# Power_Meter.net
KiCad netlist of a schematic drawn in Altium Designer
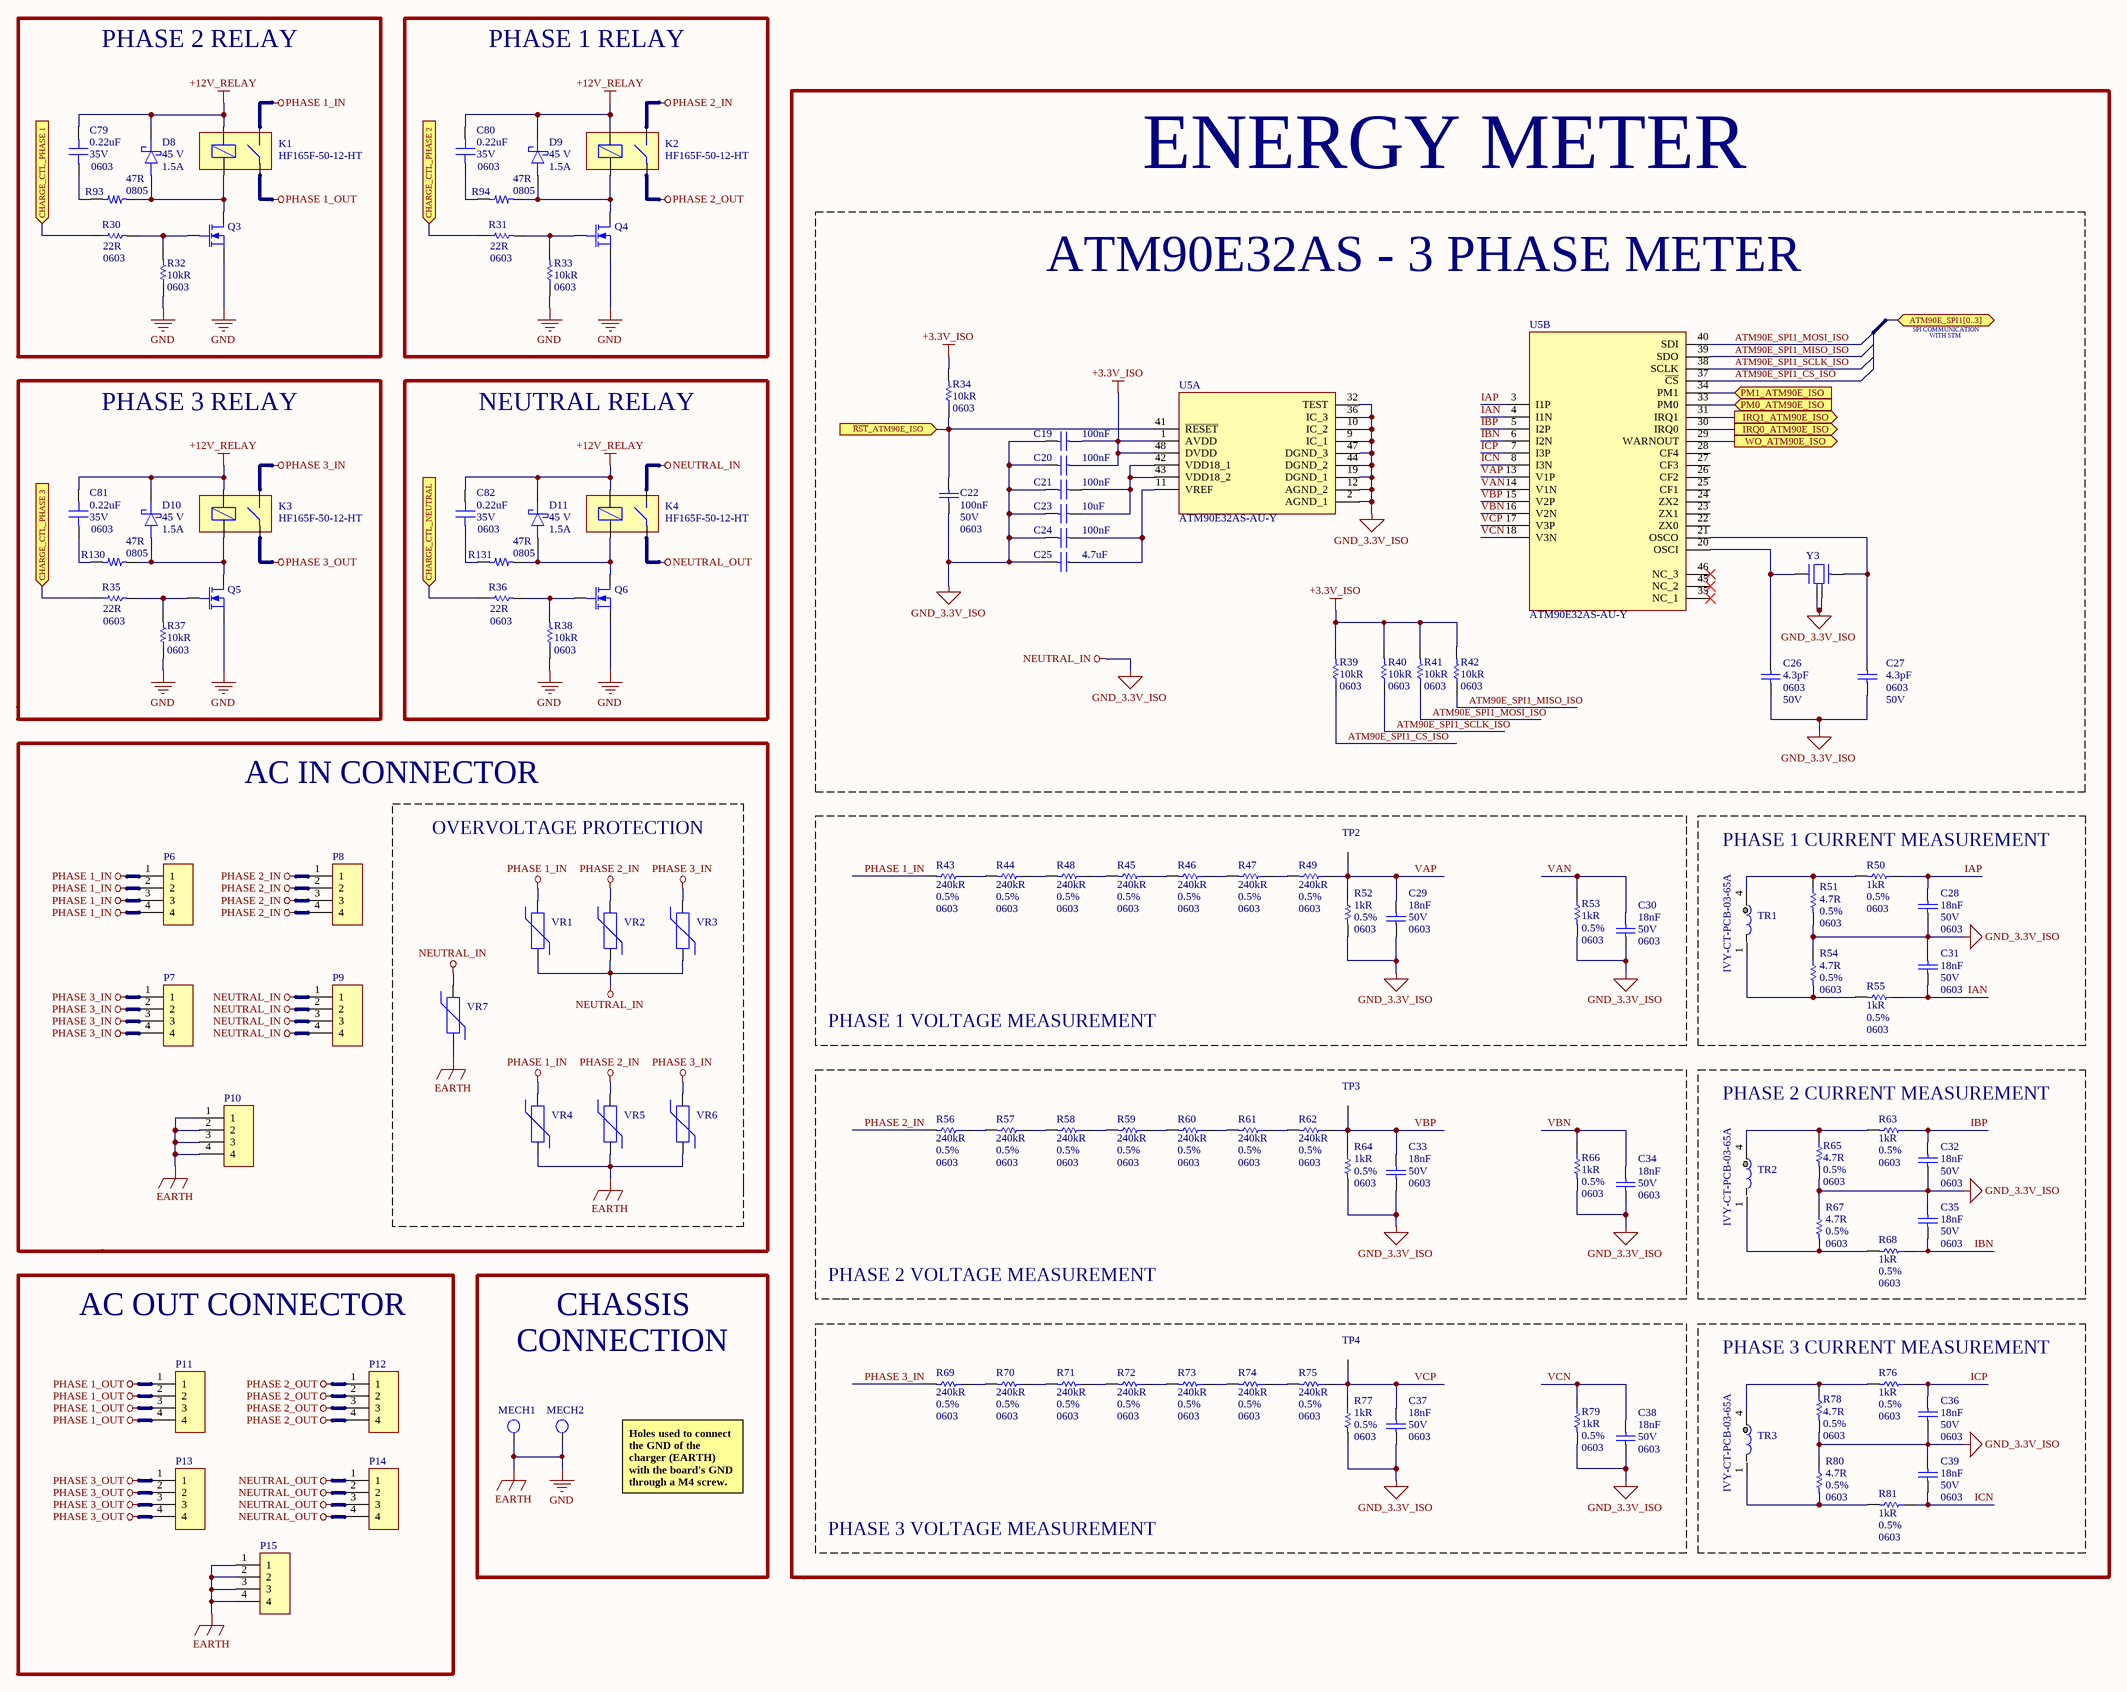
[diagram p0: Power Meter.SchDoc]

(export (version "E")
  (design (tool "Eeschema 10.0.6"))
  (components
    (comp (ref "C19")
      (value "100nF")
      (footprint "C0603")
      (description "Cap Ceramic 50V 20% +Tol 20% -Tol X7R 15% TC 0.1uF SMD 0603")
      (fields
        (field (name "MANUFACTURER") "Yageo")
        (field (name "MANUFACTURER PART NUMBER") "CC0603MRX7R9BB104")
      )
      (libsource (lib "Power2Go - REV05") (part "C_0603_0.1uF_50V_20%"))
    )
    (comp (ref "C20")
      (value "100nF")
      (footprint "C0603")
      (description "Cap Ceramic 50V 20% +Tol 20% -Tol X7R 15% TC 0.1uF SMD 0603")
      (fields
        (field (name "MANUFACTURER") "Yageo")
        (field (name "MANUFACTURER PART NUMBER") "CC0603MRX7R9BB104")
      )
      (libsource (lib "Power2Go - REV05") (part "C_0603_0.1uF_50V_20%"))
    )
    (comp (ref "C21")
      (value "100nF")
      (footprint "C0603")
      (description "Cap Ceramic 50V 20% +Tol 20% -Tol X7R 15% TC 0.1uF SMD 0603")
      (fields
        (field (name "MANUFACTURER") "Yageo")
        (field (name "MANUFACTURER PART NUMBER") "CC0603MRX7R9BB104")
      )
      (libsource (lib "Power2Go - REV05") (part "C_0603_0.1uF_50V_20%"))
    )
    (comp (ref "C22")
      (value "100nF")
      (footprint "C0603")
      (description "Cap Ceramic 50V 20% +Tol 20% -Tol X7R 15% TC 0.1uF SMD 0603")
      (fields
        (field (name "MANUFACTURER") "Yageo")
        (field (name "MANUFACTURER PART NUMBER") "CC0603MRX7R9BB104")
        (field (name "CASE/PACKAGE") "0603")
        (field (name "VOLTAGE RATING") "50V")
      )
      (libsource (lib "Power2Go - REV05") (part "C_0603_0.1uF_50V_20%"))
    )
    (comp (ref "C23")
      (value "C_0603_10uF_35V_20%")
      (footprint "C0603")
      (description "Cap Ceramic 10uF 35V X5R 20% Pad SMD 0603 85C T/R")
      (fields
        (field (name "MANUFACTURER") "Murata")
        (field (name "MANUFACTURER PART NUMBER") "GRM188R6YA106MA73D")
        (field (name "CAPACITANCE") "10uF")
      )
      (libsource (lib "Power2Go - REV05") (part "C_0603_10uF_35V_20%"))
    )
    (comp (ref "C24")
      (value "100nF")
      (footprint "C0603")
      (description "Cap Ceramic 50V 20% +Tol 20% -Tol X7R 15% TC 0.1uF SMD 0603")
      (fields
        (field (name "MANUFACTURER") "Yageo")
        (field (name "MANUFACTURER PART NUMBER") "CC0603MRX7R9BB104")
      )
      (libsource (lib "Power2Go - REV05") (part "C_0603_0.1uF_50V_20%"))
    )
    (comp (ref "C25")
      (value "4.7uF")
      (footprint "C0603")
      (description "CAP CER 4.7UF 16V X5R 0603")
      (fields
        (field (name "MANUFACTURER") "Samsung")
        (field (name "MANUFACTURER PART NUMBER") "CL10A475KO8NNNC")
      )
      (libsource (lib "Power2Go - REV05") (part "C_0603_4.7uF_16V_10%"))
    )
    (comp (ref "C26")
      (value "4.3pF")
      (footprint "C0603")
      (description "Cap Ceramic 4.3pF 50V C0G 0.25pF Pad SMD 0603 125C T/R")
      (fields
        (field (name "MANUFACTURER") "Yageo")
        (field (name "MANUFACTURER PART NUMBER") "CC0603CRNPO9BN4R3")
        (field (name "CASE CODE (IMPERIAL)") "0603")
        (field (name "VOLTAGE RATING") "50V")
      )
      (libsource (lib "Power2Go - REV05") (part "C_0603_4.3pF_±0.25pF_50V"))
    )
    (comp (ref "C27")
      (value "4.3pF")
      (footprint "C0603")
      (description "Cap Ceramic 4.3pF 50V C0G 0.25pF Pad SMD 0603 125C T/R")
      (fields
        (field (name "MANUFACTURER") "Yageo")
        (field (name "MANUFACTURER PART NUMBER") "CC0603CRNPO9BN4R3")
        (field (name "CASE CODE (IMPERIAL)") "0603")
        (field (name "VOLTAGE RATING") "50V")
      )
      (libsource (lib "Power2Go - REV05") (part "C_0603_4.3pF_±0.25pF_50V"))
    )
    (comp (ref "C28")
      (value "18nF")
      (footprint "C0603")
      (description "0603 18 nF 50 V ±5 % Tolerance X7R SMT Multilayer Ceramic Capacitor")
      (fields
        (field (name "MANUFACTURER") "Yageo")
        (field (name "MANUFACTURER PART NUMBER") "CC0603JRX7R9BB183")
        (field (name "VOLTAGE RATING") "50V")
        (field (name "CASE/PACKAGE") "0603")
      )
      (libsource (lib "Power2Go - REV05") (part "C_0603_0.018uF_50V_5%_"))
    )
    (comp (ref "C29")
      (value "18nF")
      (footprint "C0603")
      (description "0603 18 nF 50 V ±5 % Tolerance X7R SMT Multilayer Ceramic Capacitor")
      (fields
        (field (name "MANUFACTURER") "Yageo")
        (field (name "MANUFACTURER PART NUMBER") "CC0603JRX7R9BB183")
        (field (name "VOLTAGE RATING") "50V")
        (field (name "CASE/PACKAGE") "0603")
      )
      (libsource (lib "Power2Go - REV05") (part "C_0603_0.018uF_50V_5%_"))
    )
    (comp (ref "C30")
      (value "18nF")
      (footprint "C0603")
      (description "0603 18 nF 50 V ±5 % Tolerance X7R SMT Multilayer Ceramic Capacitor")
      (fields
        (field (name "MANUFACTURER") "Yageo")
        (field (name "MANUFACTURER PART NUMBER") "CC0603JRX7R9BB183")
        (field (name "VOLTAGE RATING") "50V")
        (field (name "CASE/PACKAGE") "0603")
      )
      (libsource (lib "Power2Go - REV05") (part "C_0603_0.018uF_50V_5%_"))
    )
    (comp (ref "C31")
      (value "18nF")
      (footprint "C0603")
      (description "0603 18 nF 50 V ±5 % Tolerance X7R SMT Multilayer Ceramic Capacitor")
      (fields
        (field (name "MANUFACTURER") "Yageo")
        (field (name "MANUFACTURER PART NUMBER") "CC0603JRX7R9BB183")
        (field (name "VOLTAGE RATING") "50V")
        (field (name "CASE/PACKAGE") "0603")
      )
      (libsource (lib "Power2Go - REV05") (part "C_0603_0.018uF_50V_5%_"))
    )
    (comp (ref "C32")
      (value "18nF")
      (footprint "C0603")
      (description "0603 18 nF 50 V ±5 % Tolerance X7R SMT Multilayer Ceramic Capacitor")
      (fields
        (field (name "MANUFACTURER") "Yageo")
        (field (name "MANUFACTURER PART NUMBER") "CC0603JRX7R9BB183")
        (field (name "VOLTAGE RATING") "50V")
        (field (name "CASE/PACKAGE") "0603")
      )
      (libsource (lib "Power2Go - REV05") (part "C_0603_0.018uF_50V_5%_"))
    )
    (comp (ref "C33")
      (value "18nF")
      (footprint "C0603")
      (description "0603 18 nF 50 V ±5 % Tolerance X7R SMT Multilayer Ceramic Capacitor")
      (fields
        (field (name "MANUFACTURER") "Yageo")
        (field (name "MANUFACTURER PART NUMBER") "CC0603JRX7R9BB183")
        (field (name "VOLTAGE RATING") "50V")
        (field (name "CASE/PACKAGE") "0603")
      )
      (libsource (lib "Power2Go - REV05") (part "C_0603_0.018uF_50V_5%_"))
    )
    (comp (ref "C34")
      (value "18nF")
      (footprint "C0603")
      (description "0603 18 nF 50 V ±5 % Tolerance X7R SMT Multilayer Ceramic Capacitor")
      (fields
        (field (name "MANUFACTURER") "Yageo")
        (field (name "MANUFACTURER PART NUMBER") "CC0603JRX7R9BB183")
        (field (name "VOLTAGE RATING") "50V")
        (field (name "CASE/PACKAGE") "0603")
      )
      (libsource (lib "Power2Go - REV05") (part "C_0603_0.018uF_50V_5%_"))
    )
    (comp (ref "C35")
      (value "18nF")
      (footprint "C0603")
      (description "0603 18 nF 50 V ±5 % Tolerance X7R SMT Multilayer Ceramic Capacitor")
      (fields
        (field (name "MANUFACTURER") "Yageo")
        (field (name "MANUFACTURER PART NUMBER") "CC0603JRX7R9BB183")
        (field (name "VOLTAGE RATING") "50V")
        (field (name "CASE/PACKAGE") "0603")
      )
      (libsource (lib "Power2Go - REV05") (part "C_0603_0.018uF_50V_5%_"))
    )
    (comp (ref "C36")
      (value "18nF")
      (footprint "C0603")
      (description "0603 18 nF 50 V ±5 % Tolerance X7R SMT Multilayer Ceramic Capacitor")
      (fields
        (field (name "MANUFACTURER") "Yageo")
        (field (name "MANUFACTURER PART NUMBER") "CC0603JRX7R9BB183")
        (field (name "VOLTAGE RATING") "50V")
        (field (name "CASE/PACKAGE") "0603")
      )
      (libsource (lib "Power2Go - REV05") (part "C_0603_0.018uF_50V_5%_"))
    )
    (comp (ref "C37")
      (value "18nF")
      (footprint "C0603")
      (description "0603 18 nF 50 V ±5 % Tolerance X7R SMT Multilayer Ceramic Capacitor")
      (fields
        (field (name "MANUFACTURER") "Yageo")
        (field (name "MANUFACTURER PART NUMBER") "CC0603JRX7R9BB183")
        (field (name "VOLTAGE RATING") "50V")
        (field (name "CASE/PACKAGE") "0603")
      )
      (libsource (lib "Power2Go - REV05") (part "C_0603_0.018uF_50V_5%_"))
    )
    (comp (ref "C38")
      (value "18nF")
      (footprint "C0603")
      (description "0603 18 nF 50 V ±5 % Tolerance X7R SMT Multilayer Ceramic Capacitor")
      (fields
        (field (name "MANUFACTURER") "Yageo")
        (field (name "MANUFACTURER PART NUMBER") "CC0603JRX7R9BB183")
        (field (name "VOLTAGE RATING") "50V")
        (field (name "CASE/PACKAGE") "0603")
      )
      (libsource (lib "Power2Go - REV05") (part "C_0603_0.018uF_50V_5%_"))
    )
    (comp (ref "C39")
      (value "18nF")
      (footprint "C0603")
      (description "0603 18 nF 50 V ±5 % Tolerance X7R SMT Multilayer Ceramic Capacitor")
      (fields
        (field (name "MANUFACTURER") "Yageo")
        (field (name "MANUFACTURER PART NUMBER") "CC0603JRX7R9BB183")
        (field (name "VOLTAGE RATING") "50V")
        (field (name "CASE/PACKAGE") "0603")
      )
      (libsource (lib "Power2Go - REV05") (part "C_0603_0.018uF_50V_5%_"))
    )
    (comp (ref "C79")
      (value "Capacitor")
      (footprint "CAPC 0603/1608")
      (description "CAPACITOR SMD CERÂMICO 0.22uF 35V X7R 0603")
      (fields
        (field (name "MANUFACTURER PART NUMBER") "C1608X7R1V224K080AB")
        (field (name "PARAMETER 1") "0.22uF")
        (field (name "PARAMETER 2") "35V")
        (field (name "MANUFACTURER") "TDK")
        (field (name "PACKAGE") "0603")
        (field (name "AUTHOR") "Esdras Bahiano")
      )
      (libsource (lib "LIB_DE_COMPONENTES") (part "Capacitor"))
    )
    (comp (ref "C80")
      (value "Capacitor")
      (footprint "CAPC 0603/1608")
      (description "CAPACITOR SMD CERÂMICO 0.22uF 35V X7R 0603")
      (fields
        (field (name "MANUFACTURER PART NUMBER") "C1608X7R1V224K080AB")
        (field (name "PARAMETER 1") "0.22uF")
        (field (name "PARAMETER 2") "35V")
        (field (name "MANUFACTURER") "TDK")
        (field (name "PACKAGE") "0603")
        (field (name "AUTHOR") "Esdras Bahiano")
      )
      (libsource (lib "LIB_DE_COMPONENTES") (part "Capacitor"))
    )
    (comp (ref "C81")
      (value "Capacitor")
      (footprint "CAPC 0603/1608")
      (description "CAPACITOR SMD CERÂMICO 0.22uF 35V X7R 0603")
      (fields
        (field (name "MANUFACTURER PART NUMBER") "C1608X7R1V224K080AB")
        (field (name "PARAMETER 1") "0.22uF")
        (field (name "PARAMETER 2") "35V")
        (field (name "MANUFACTURER") "TDK")
        (field (name "PACKAGE") "0603")
        (field (name "AUTHOR") "Esdras Bahiano")
      )
      (libsource (lib "LIB_DE_COMPONENTES") (part "Capacitor"))
    )
    (comp (ref "C82")
      (value "Capacitor")
      (footprint "CAPC 0603/1608")
      (description "CAPACITOR SMD CERÂMICO 0.22uF 35V X7R 0603")
      (fields
        (field (name "MANUFACTURER PART NUMBER") "C1608X7R1V224K080AB")
        (field (name "PARAMETER 1") "0.22uF")
        (field (name "PARAMETER 2") "35V")
        (field (name "MANUFACTURER") "TDK")
        (field (name "PACKAGE") "0603")
        (field (name "AUTHOR") "Esdras Bahiano")
      )
      (libsource (lib "LIB_DE_COMPONENTES") (part "Capacitor"))
    )
    (comp (ref "D8")
      (value "BYS10-45HE3_A/H")
      (footprint "DO-214AC-2")
      (description "Rectifier Diode Schottky 45V 1.5A Automotive 2-Pin SMA T/R")
      (fields
        (field (name "MANUFACTURER") "Vishay Semiconductors")
        (field (name "VOLTAGE") "45 V")
        (field (name "CURRENT") "1.5A")
      )
      (libsource (lib "Power2Go - REV05") (part "D_Schottky_BYS10-45HE3_A/H"))
    )
    (comp (ref "D9")
      (value "BYS10-45HE3_A/H")
      (footprint "DO-214AC-2")
      (description "Rectifier Diode Schottky 45V 1.5A Automotive 2-Pin SMA T/R")
      (fields
        (field (name "MANUFACTURER") "Vishay Semiconductors")
        (field (name "VOLTAGE") "45 V")
        (field (name "CURRENT") "1.5A")
      )
      (libsource (lib "Power2Go - REV05") (part "D_Schottky_BYS10-45HE3_A/H"))
    )
    (comp (ref "D10")
      (value "BYS10-45HE3_A/H")
      (footprint "DO-214AC-2")
      (description "Rectifier Diode Schottky 45V 1.5A Automotive 2-Pin SMA T/R")
      (fields
        (field (name "MANUFACTURER") "Vishay Semiconductors")
        (field (name "VOLTAGE") "45 V")
        (field (name "CURRENT") "1.5A")
      )
      (libsource (lib "Power2Go - REV05") (part "D_Schottky_BYS10-45HE3_A/H"))
    )
    (comp (ref "D11")
      (value "BYS10-45HE3_A/H")
      (footprint "DO-214AC-2")
      (description "Rectifier Diode Schottky 45V 1.5A Automotive 2-Pin SMA T/R")
      (fields
        (field (name "MANUFACTURER") "Vishay Semiconductors")
        (field (name "VOLTAGE") "45 V")
        (field (name "CURRENT") "1.5A")
      )
      (libsource (lib "Power2Go - REV05") (part "D_Schottky_BYS10-45HE3_A/H"))
    )
    (comp (ref "K1")
      (value "HF165F-50-12-HT")
      (footprint "HF165F-50 12-HT")
      (description "RELË PTH POWER 50A , Coil 12 V 120 Ohms")
      (fields
        (field (name "MANUFACTURER") "HONGFA")
        (field (name "MANUFACTURER PART NUMBER") "HF165F-50 12-HT")
        (field (name "AUTHOR") "Jovelino Torres")
      )
      (libsource (lib "LIB_DE_COMPONENTES") (part "Relay"))
    )
    (comp (ref "K2")
      (value "HF165F-50-12-HT")
      (footprint "HF165F-50 12-HT")
      (description "RELË PTH POWER 50A , Coil 12 V 120 Ohms")
      (fields
        (field (name "MANUFACTURER") "HONGFA")
        (field (name "MANUFACTURER PART NUMBER") "HF165F-50 12-HT")
        (field (name "AUTHOR") "Jovelino Torres")
      )
      (libsource (lib "LIB_DE_COMPONENTES") (part "Relay"))
    )
    (comp (ref "K3")
      (value "HF165F-50-12-HT")
      (footprint "HF165F-50 12-HT")
      (description "RELË PTH POWER 50A , Coil 12 V 120 Ohms")
      (fields
        (field (name "MANUFACTURER") "HONGFA")
        (field (name "MANUFACTURER PART NUMBER") "HF165F-50 12-HT")
        (field (name "AUTHOR") "Jovelino Torres")
      )
      (libsource (lib "LIB_DE_COMPONENTES") (part "Relay"))
    )
    (comp (ref "K4")
      (value "HF165F-50-12-HT")
      (footprint "HF165F-50 12-HT")
      (description "RELË PTH POWER 50A , Coil 12 V 120 Ohms")
      (fields
        (field (name "MANUFACTURER") "HONGFA")
        (field (name "MANUFACTURER PART NUMBER") "HF165F-50 12-HT")
        (field (name "AUTHOR") "Jovelino Torres")
      )
      (libsource (lib "LIB_DE_COMPONENTES") (part "Relay"))
    )
    (comp (ref "MECH1")
      (value "MECH-Screw-M4")
      (footprint "MECH-M4")
      (description "PCB Fastener Screws M4")
      (libsource (lib "Power2Go - REV05") (part "MECH_Screw_M4"))
    )
    (comp (ref "MECH2")
      (value "MECH-Screw-M4")
      (footprint "MECH-M4")
      (description "PCB Fastener Screws M4")
      (libsource (lib "Power2Go - REV05") (part "MECH_Screw_M4"))
    )
    (comp (ref "P6")
      (value "PCB-15")
      (footprint "Connector POWER PCB-15")
      (libsource (lib "Power2Go - REV05") (part "P_PWRCONN_M5-SCREW_4PIN"))
    )
    (comp (ref "P7")
      (value "PCB-15")
      (footprint "Connector POWER PCB-15")
      (libsource (lib "Power2Go - REV05") (part "P_PWRCONN_M5-SCREW_4PIN"))
    )
    (comp (ref "P8")
      (value "PCB-15")
      (footprint "Connector POWER PCB-15")
      (libsource (lib "Power2Go - REV05") (part "P_PWRCONN_M5-SCREW_4PIN"))
    )
    (comp (ref "P9")
      (value "PCB-15")
      (footprint "Connector POWER PCB-15")
      (libsource (lib "Power2Go - REV05") (part "P_PWRCONN_M5-SCREW_4PIN"))
    )
    (comp (ref "P10")
      (value "PCB-15")
      (footprint "Connector POWER PCB-15")
      (libsource (lib "Power2Go - REV05") (part "P_PWRCONN_M5-SCREW_4PIN"))
    )
    (comp (ref "P11")
      (value "PCB-15")
      (footprint "Connector POWER PCB-15")
      (libsource (lib "Power2Go - REV05") (part "P_PWRCONN_M5-SCREW_4PIN"))
    )
    (comp (ref "P12")
      (value "PCB-15")
      (footprint "Connector POWER PCB-15")
      (libsource (lib "Power2Go - REV05") (part "P_PWRCONN_M5-SCREW_4PIN"))
    )
    (comp (ref "P13")
      (value "PCB-15")
      (footprint "Connector POWER PCB-15")
      (libsource (lib "Power2Go - REV05") (part "P_PWRCONN_M5-SCREW_4PIN"))
    )
    (comp (ref "P14")
      (value "PCB-15")
      (footprint "Connector POWER PCB-15")
      (libsource (lib "Power2Go - REV05") (part "P_PWRCONN_M5-SCREW_4PIN"))
    )
    (comp (ref "P15")
      (value "PCB-15")
      (footprint "Connector POWER PCB-15")
      (libsource (lib "Power2Go - REV05") (part "P_PWRCONN_M5-SCREW_4PIN"))
    )
    (comp (ref "Q3")
      (value "RSF015N06FRATL")
      (footprint "TUMT-3")
      (description "Transistor Mosfet N-ch 60V 1.5A 3-PIN Tumt T/r")
      (fields (field (name "MANUFACTURER") "Rohm"))
      (libsource (lib "Power2Go - REV05") (part "Q_RSF015N06FRATL_TUMT-3"))
    )
    (comp (ref "Q4")
      (value "RSF015N06FRATL")
      (footprint "TUMT-3")
      (description "Transistor Mosfet N-ch 60V 1.5A 3-PIN Tumt T/r")
      (fields (field (name "MANUFACTURER") "Rohm"))
      (libsource (lib "Power2Go - REV05") (part "Q_RSF015N06FRATL_TUMT-3"))
    )
    (comp (ref "Q5")
      (value "RSF015N06FRATL")
      (footprint "TUMT-3")
      (description "Transistor Mosfet N-ch 60V 1.5A 3-PIN Tumt T/r")
      (fields (field (name "MANUFACTURER") "Rohm"))
      (libsource (lib "Power2Go - REV05") (part "Q_RSF015N06FRATL_TUMT-3"))
    )
    (comp (ref "Q6")
      (value "RSF015N06FRATL")
      (footprint "TUMT-3")
      (description "Transistor Mosfet N-ch 60V 1.5A 3-PIN Tumt T/r")
      (fields (field (name "MANUFACTURER") "Rohm"))
      (libsource (lib "Power2Go - REV05") (part "Q_RSF015N06FRATL_TUMT-3"))
    )
    (comp (ref "R30")
      (value "CRCW060322R0FKEAC")
      (footprint "R0603")
      (description "Thick Film Resistors - SMD 1/10Watt 22ohms 1% Commercial Use")
      (fields
        (field (name "MANUFACTURER") "Vishay")
        (field (name "TOLERANCE") "1%")
        (field (name "RESISTANCE") "22R")
        (field (name "CASE CODE (IMPERIAL)") "0603")
      )
      (libsource (lib "Power2Go - REV05") (part "R_0603_22R_1%_1/10W"))
    )
    (comp (ref "R31")
      (value "CRCW060322R0FKEAC")
      (footprint "R0603")
      (description "Thick Film Resistors - SMD 1/10Watt 22ohms 1% Commercial Use")
      (fields
        (field (name "MANUFACTURER") "Vishay")
        (field (name "TOLERANCE") "1%")
        (field (name "RESISTANCE") "22R")
        (field (name "CASE CODE (IMPERIAL)") "0603")
      )
      (libsource (lib "Power2Go - REV05") (part "R_0603_22R_1%_1/10W"))
    )
    (comp (ref "R32")
      (value "10kR")
      (footprint "R0603")
      (fields
        (field (name "MANUFACTURER") "Vishay")
        (field (name "MANUFACTURER PART NUMBER") "CRCW060310K0JNEBC")
        (field (name "TOLERANCE") "5%")
        (field (name "CASE/PACKAGE") "0603")
      )
      (libsource (lib "Power2Go - REV05") (part "R_0603_10kR_5%_1/10W"))
    )
    (comp (ref "R33")
      (value "10kR")
      (footprint "R0603")
      (fields
        (field (name "MANUFACTURER") "Vishay")
        (field (name "MANUFACTURER PART NUMBER") "CRCW060310K0JNEBC")
        (field (name "TOLERANCE") "5%")
        (field (name "CASE/PACKAGE") "0603")
      )
      (libsource (lib "Power2Go - REV05") (part "R_0603_10kR_5%_1/10W"))
    )
    (comp (ref "R34")
      (value "10kR")
      (footprint "R0603")
      (fields
        (field (name "MANUFACTURER") "Vishay")
        (field (name "MANUFACTURER PART NUMBER") "CRCW060310K0JNEBC")
        (field (name "TOLERANCE") "5%")
        (field (name "CASE/PACKAGE") "0603")
      )
      (libsource (lib "Power2Go - REV05") (part "R_0603_10kR_5%_1/10W"))
    )
    (comp (ref "R35")
      (value "CRCW060322R0FKEAC")
      (footprint "R0603")
      (description "Thick Film Resistors - SMD 1/10Watt 22ohms 1% Commercial Use")
      (fields
        (field (name "MANUFACTURER") "Vishay")
        (field (name "TOLERANCE") "1%")
        (field (name "RESISTANCE") "22R")
        (field (name "CASE CODE (IMPERIAL)") "0603")
      )
      (libsource (lib "Power2Go - REV05") (part "R_0603_22R_1%_1/10W"))
    )
    (comp (ref "R36")
      (value "CRCW060322R0FKEAC")
      (footprint "R0603")
      (description "Thick Film Resistors - SMD 1/10Watt 22ohms 1% Commercial Use")
      (fields
        (field (name "MANUFACTURER") "Vishay")
        (field (name "TOLERANCE") "1%")
        (field (name "RESISTANCE") "22R")
        (field (name "CASE CODE (IMPERIAL)") "0603")
      )
      (libsource (lib "Power2Go - REV05") (part "R_0603_22R_1%_1/10W"))
    )
    (comp (ref "R37")
      (value "10kR")
      (footprint "R0603")
      (fields
        (field (name "MANUFACTURER") "Vishay")
        (field (name "MANUFACTURER PART NUMBER") "CRCW060310K0JNEBC")
        (field (name "TOLERANCE") "5%")
        (field (name "CASE/PACKAGE") "0603")
      )
      (libsource (lib "Power2Go - REV05") (part "R_0603_10kR_5%_1/10W"))
    )
    (comp (ref "R38")
      (value "10kR")
      (footprint "R0603")
      (fields
        (field (name "MANUFACTURER") "Vishay")
        (field (name "MANUFACTURER PART NUMBER") "CRCW060310K0JNEBC")
        (field (name "TOLERANCE") "5%")
        (field (name "CASE/PACKAGE") "0603")
      )
      (libsource (lib "Power2Go - REV05") (part "R_0603_10kR_5%_1/10W"))
    )
    (comp (ref "R39")
      (value "10kR")
      (footprint "R0603")
      (fields
        (field (name "MANUFACTURER") "Vishay")
        (field (name "MANUFACTURER PART NUMBER") "CRCW060310K0JNEBC")
        (field (name "TOLERANCE") "5%")
        (field (name "CASE/PACKAGE") "0603")
      )
      (libsource (lib "Power2Go - REV05") (part "R_0603_10kR_5%_1/10W"))
    )
    (comp (ref "R40")
      (value "10kR")
      (footprint "R0603")
      (fields
        (field (name "MANUFACTURER") "Vishay")
        (field (name "MANUFACTURER PART NUMBER") "CRCW060310K0JNEBC")
        (field (name "TOLERANCE") "5%")
        (field (name "CASE/PACKAGE") "0603")
      )
      (libsource (lib "Power2Go - REV05") (part "R_0603_10kR_5%_1/10W"))
    )
    (comp (ref "R41")
      (value "10kR")
      (footprint "R0603")
      (fields
        (field (name "MANUFACTURER") "Vishay")
        (field (name "MANUFACTURER PART NUMBER") "CRCW060310K0JNEBC")
        (field (name "TOLERANCE") "5%")
        (field (name "CASE/PACKAGE") "0603")
      )
      (libsource (lib "Power2Go - REV05") (part "R_0603_10kR_5%_1/10W"))
    )
    (comp (ref "R42")
      (value "10kR")
      (footprint "R0603")
      (fields
        (field (name "MANUFACTURER") "Vishay")
        (field (name "MANUFACTURER PART NUMBER") "CRCW060310K0JNEBC")
        (field (name "TOLERANCE") "5%")
        (field (name "CASE/PACKAGE") "0603")
      )
      (libsource (lib "Power2Go - REV05") (part "R_0603_10kR_5%_1/10W"))
    )
    (comp (ref "R43")
      (value "240kR")
      (footprint "R0603")
      (description "Res Thin Film 1.6 x 0.8 mm 240K Ohm 0.5% 0.063W(1/16W) 25ppm/ C Molded SMD T/R")
      (fields
        (field (name "MANUFACTURER") "Susumu")
        (field (name "MANUFACTURER PART NUMBER") "RR0816P-244-D")
        (field (name "TOLERANCE") "0.5%")
        (field (name "CASE CODE (IMPERIAL)") "0603")
      )
      (libsource (lib "Power2Go - REV05") (part "R_0603_240kR_0.5%_1/16W_25PPM"))
    )
    (comp (ref "R44")
      (value "240kR")
      (footprint "R0603")
      (description "Res Thin Film 1.6 x 0.8 mm 240K Ohm 0.5% 0.063W(1/16W) 25ppm/ C Molded SMD T/R")
      (fields
        (field (name "MANUFACTURER") "Susumu")
        (field (name "MANUFACTURER PART NUMBER") "RR0816P-244-D")
        (field (name "TOLERANCE") "0.5%")
        (field (name "CASE CODE (IMPERIAL)") "0603")
      )
      (libsource (lib "Power2Go - REV05") (part "R_0603_240kR_0.5%_1/16W_25PPM"))
    )
    (comp (ref "R45")
      (value "240kR")
      (footprint "R0603")
      (description "Res Thin Film 1.6 x 0.8 mm 240K Ohm 0.5% 0.063W(1/16W) 25ppm/ C Molded SMD T/R")
      (fields
        (field (name "MANUFACTURER") "Susumu")
        (field (name "MANUFACTURER PART NUMBER") "RR0816P-244-D")
        (field (name "TOLERANCE") "0.5%")
        (field (name "CASE CODE (IMPERIAL)") "0603")
      )
      (libsource (lib "Power2Go - REV05") (part "R_0603_240kR_0.5%_1/16W_25PPM"))
    )
    (comp (ref "R46")
      (value "240kR")
      (footprint "R0603")
      (description "Res Thin Film 1.6 x 0.8 mm 240K Ohm 0.5% 0.063W(1/16W) 25ppm/ C Molded SMD T/R")
      (fields
        (field (name "MANUFACTURER") "Susumu")
        (field (name "MANUFACTURER PART NUMBER") "RR0816P-244-D")
        (field (name "TOLERANCE") "0.5%")
        (field (name "CASE CODE (IMPERIAL)") "0603")
      )
      (libsource (lib "Power2Go - REV05") (part "R_0603_240kR_0.5%_1/16W_25PPM"))
    )
    (comp (ref "R47")
      (value "240kR")
      (footprint "R0603")
      (description "Res Thin Film 1.6 x 0.8 mm 240K Ohm 0.5% 0.063W(1/16W) 25ppm/ C Molded SMD T/R")
      (fields
        (field (name "MANUFACTURER") "Susumu")
        (field (name "MANUFACTURER PART NUMBER") "RR0816P-244-D")
        (field (name "TOLERANCE") "0.5%")
        (field (name "CASE CODE (IMPERIAL)") "0603")
      )
      (libsource (lib "Power2Go - REV05") (part "R_0603_240kR_0.5%_1/16W_25PPM"))
    )
    (comp (ref "R48")
      (value "240kR")
      (footprint "R0603")
      (description "Res Thin Film 1.6 x 0.8 mm 240K Ohm 0.5% 0.063W(1/16W) 25ppm/ C Molded SMD T/R")
      (fields
        (field (name "MANUFACTURER") "Susumu")
        (field (name "MANUFACTURER PART NUMBER") "RR0816P-244-D")
        (field (name "TOLERANCE") "0.5%")
        (field (name "CASE CODE (IMPERIAL)") "0603")
      )
      (libsource (lib "Power2Go - REV05") (part "R_0603_240kR_0.5%_1/16W_25PPM"))
    )
    (comp (ref "R49")
      (value "240kR")
      (footprint "R0603")
      (description "Res Thin Film 1.6 x 0.8 mm 240K Ohm 0.5% 0.063W(1/16W) 25ppm/ C Molded SMD T/R")
      (fields
        (field (name "MANUFACTURER") "Susumu")
        (field (name "MANUFACTURER PART NUMBER") "RR0816P-244-D")
        (field (name "TOLERANCE") "0.5%")
        (field (name "CASE CODE (IMPERIAL)") "0603")
      )
      (libsource (lib "Power2Go - REV05") (part "R_0603_240kR_0.5%_1/16W_25PPM"))
    )
    (comp (ref "R50")
      (value "1kR")
      (footprint "R0603")
      (description "Res Thin Film 0603 1K Ohm 0.5% 0.063W(1/16W) ±25ppm/C Pad SMD Automotive T/R")
      (fields
        (field (name "MANUFACTURER") "Susumu")
        (field (name "MANUFACTURER PART NUMBER") "RR0816P-102-D")
        (field (name "CASE/PACKAGE") "0603")
        (field (name "RESISTANCE TOLERANCE") "0.5%")
      )
      (libsource (lib "Power2Go - REV05") (part "R_0603_1kR_0.5%_1/16W_25PPM"))
    )
    (comp (ref "R51")
      (value "4.7R")
      (footprint "R0603")
      (description "High Precision-High Stability Chip Resistor Thin Film 0603 4.7Ohm 0.5% Paper T/R")
      (fields
        (field (name "MANUFACTURER") "Yageo")
        (field (name "MANUFACTURER PART NUMBER") "RT0603DRD074R7L")
        (field (name "TOLERANCE") "0.5%")
        (field (name "CASE/PACKAGE") "0603")
      )
      (libsource (lib "Power2Go - REV05") (part "R_0603_4.7R_0.5%_1/10W"))
    )
    (comp (ref "R52")
      (value "1kR")
      (footprint "R0603")
      (description "Res Thin Film 0603 1K Ohm 0.5% 0.063W(1/16W) ±25ppm/C Pad SMD Automotive T/R")
      (fields
        (field (name "MANUFACTURER") "Susumu")
        (field (name "MANUFACTURER PART NUMBER") "RR0816P-102-D")
        (field (name "CASE/PACKAGE") "0603")
        (field (name "RESISTANCE TOLERANCE") "0.5%")
      )
      (libsource (lib "Power2Go - REV05") (part "R_0603_1kR_0.5%_1/16W_25PPM"))
    )
    (comp (ref "R53")
      (value "1kR")
      (footprint "R0603")
      (description "Res Thin Film 0603 1K Ohm 0.5% 0.063W(1/16W) ±25ppm/C Pad SMD Automotive T/R")
      (fields
        (field (name "MANUFACTURER") "Susumu")
        (field (name "MANUFACTURER PART NUMBER") "RR0816P-102-D")
        (field (name "CASE/PACKAGE") "0603")
        (field (name "RESISTANCE TOLERANCE") "0.5%")
      )
      (libsource (lib "Power2Go - REV05") (part "R_0603_1kR_0.5%_1/16W_25PPM"))
    )
    (comp (ref "R54")
      (value "4.7R")
      (footprint "R0603")
      (description "High Precision-High Stability Chip Resistor Thin Film 0603 4.7Ohm 0.5% Paper T/R")
      (fields
        (field (name "MANUFACTURER") "Yageo")
        (field (name "MANUFACTURER PART NUMBER") "RT0603DRD074R7L")
        (field (name "TOLERANCE") "0.5%")
        (field (name "CASE/PACKAGE") "0603")
      )
      (libsource (lib "Power2Go - REV05") (part "R_0603_4.7R_0.5%_1/10W"))
    )
    (comp (ref "R55")
      (value "1kR")
      (footprint "R0603")
      (description "Res Thin Film 0603 1K Ohm 0.5% 0.063W(1/16W) ±25ppm/C Pad SMD Automotive T/R")
      (fields
        (field (name "MANUFACTURER") "Susumu")
        (field (name "MANUFACTURER PART NUMBER") "RR0816P-102-D")
        (field (name "CASE/PACKAGE") "0603")
        (field (name "RESISTANCE TOLERANCE") "0.5%")
      )
      (libsource (lib "Power2Go - REV05") (part "R_0603_1kR_0.5%_1/16W_25PPM"))
    )
    (comp (ref "R56")
      (value "240kR")
      (footprint "R0603")
      (description "Res Thin Film 1.6 x 0.8 mm 240K Ohm 0.5% 0.063W(1/16W) 25ppm/ C Molded SMD T/R")
      (fields
        (field (name "MANUFACTURER") "Susumu")
        (field (name "MANUFACTURER PART NUMBER") "RR0816P-244-D")
        (field (name "TOLERANCE") "0.5%")
        (field (name "CASE CODE (IMPERIAL)") "0603")
      )
      (libsource (lib "Power2Go - REV05") (part "R_0603_240kR_0.5%_1/16W_25PPM"))
    )
    (comp (ref "R57")
      (value "240kR")
      (footprint "R0603")
      (description "Res Thin Film 1.6 x 0.8 mm 240K Ohm 0.5% 0.063W(1/16W) 25ppm/ C Molded SMD T/R")
      (fields
        (field (name "MANUFACTURER") "Susumu")
        (field (name "MANUFACTURER PART NUMBER") "RR0816P-244-D")
        (field (name "TOLERANCE") "0.5%")
        (field (name "CASE CODE (IMPERIAL)") "0603")
      )
      (libsource (lib "Power2Go - REV05") (part "R_0603_240kR_0.5%_1/16W_25PPM"))
    )
    (comp (ref "R58")
      (value "240kR")
      (footprint "R0603")
      (description "Res Thin Film 1.6 x 0.8 mm 240K Ohm 0.5% 0.063W(1/16W) 25ppm/ C Molded SMD T/R")
      (fields
        (field (name "MANUFACTURER") "Susumu")
        (field (name "MANUFACTURER PART NUMBER") "RR0816P-244-D")
        (field (name "TOLERANCE") "0.5%")
        (field (name "CASE CODE (IMPERIAL)") "0603")
      )
      (libsource (lib "Power2Go - REV05") (part "R_0603_240kR_0.5%_1/16W_25PPM"))
    )
    (comp (ref "R59")
      (value "240kR")
      (footprint "R0603")
      (description "Res Thin Film 1.6 x 0.8 mm 240K Ohm 0.5% 0.063W(1/16W) 25ppm/ C Molded SMD T/R")
      (fields
        (field (name "MANUFACTURER") "Susumu")
        (field (name "MANUFACTURER PART NUMBER") "RR0816P-244-D")
        (field (name "TOLERANCE") "0.5%")
        (field (name "CASE CODE (IMPERIAL)") "0603")
      )
      (libsource (lib "Power2Go - REV05") (part "R_0603_240kR_0.5%_1/16W_25PPM"))
    )
    (comp (ref "R60")
      (value "240kR")
      (footprint "R0603")
      (description "Res Thin Film 1.6 x 0.8 mm 240K Ohm 0.5% 0.063W(1/16W) 25ppm/ C Molded SMD T/R")
      (fields
        (field (name "MANUFACTURER") "Susumu")
        (field (name "MANUFACTURER PART NUMBER") "RR0816P-244-D")
        (field (name "TOLERANCE") "0.5%")
        (field (name "CASE CODE (IMPERIAL)") "0603")
      )
      (libsource (lib "Power2Go - REV05") (part "R_0603_240kR_0.5%_1/16W_25PPM"))
    )
    (comp (ref "R61")
      (value "240kR")
      (footprint "R0603")
      (description "Res Thin Film 1.6 x 0.8 mm 240K Ohm 0.5% 0.063W(1/16W) 25ppm/ C Molded SMD T/R")
      (fields
        (field (name "MANUFACTURER") "Susumu")
        (field (name "MANUFACTURER PART NUMBER") "RR0816P-244-D")
        (field (name "TOLERANCE") "0.5%")
        (field (name "CASE CODE (IMPERIAL)") "0603")
      )
      (libsource (lib "Power2Go - REV05") (part "R_0603_240kR_0.5%_1/16W_25PPM"))
    )
    (comp (ref "R62")
      (value "240kR")
      (footprint "R0603")
      (description "Res Thin Film 1.6 x 0.8 mm 240K Ohm 0.5% 0.063W(1/16W) 25ppm/ C Molded SMD T/R")
      (fields
        (field (name "MANUFACTURER") "Susumu")
        (field (name "MANUFACTURER PART NUMBER") "RR0816P-244-D")
        (field (name "TOLERANCE") "0.5%")
        (field (name "CASE CODE (IMPERIAL)") "0603")
      )
      (libsource (lib "Power2Go - REV05") (part "R_0603_240kR_0.5%_1/16W_25PPM"))
    )
    (comp (ref "R63")
      (value "1kR")
      (footprint "R0603")
      (description "Res Thin Film 0603 1K Ohm 0.5% 0.063W(1/16W) ±25ppm/C Pad SMD Automotive T/R")
      (fields
        (field (name "MANUFACTURER") "Susumu")
        (field (name "MANUFACTURER PART NUMBER") "RR0816P-102-D")
        (field (name "CASE/PACKAGE") "0603")
        (field (name "RESISTANCE TOLERANCE") "0.5%")
      )
      (libsource (lib "Power2Go - REV05") (part "R_0603_1kR_0.5%_1/16W_25PPM"))
    )
    (comp (ref "R64")
      (value "1kR")
      (footprint "R0603")
      (description "Res Thin Film 0603 1K Ohm 0.5% 0.063W(1/16W) ±25ppm/C Pad SMD Automotive T/R")
      (fields
        (field (name "MANUFACTURER") "Susumu")
        (field (name "MANUFACTURER PART NUMBER") "RR0816P-102-D")
        (field (name "CASE/PACKAGE") "0603")
        (field (name "RESISTANCE TOLERANCE") "0.5%")
      )
      (libsource (lib "Power2Go - REV05") (part "R_0603_1kR_0.5%_1/16W_25PPM"))
    )
    (comp (ref "R65")
      (value "4.7R")
      (footprint "R0603")
      (description "High Precision-High Stability Chip Resistor Thin Film 0603 4.7Ohm 0.5% Paper T/R")
      (fields
        (field (name "MANUFACTURER") "Yageo")
        (field (name "MANUFACTURER PART NUMBER") "RT0603DRD074R7L")
        (field (name "TOLERANCE") "0.5%")
        (field (name "CASE/PACKAGE") "0603")
      )
      (libsource (lib "Power2Go - REV05") (part "R_0603_4.7R_0.5%_1/10W"))
    )
    (comp (ref "R66")
      (value "1kR")
      (footprint "R0603")
      (description "Res Thin Film 0603 1K Ohm 0.5% 0.063W(1/16W) ±25ppm/C Pad SMD Automotive T/R")
      (fields
        (field (name "MANUFACTURER") "Susumu")
        (field (name "MANUFACTURER PART NUMBER") "RR0816P-102-D")
        (field (name "CASE/PACKAGE") "0603")
        (field (name "RESISTANCE TOLERANCE") "0.5%")
      )
      (libsource (lib "Power2Go - REV05") (part "R_0603_1kR_0.5%_1/16W_25PPM"))
    )
    (comp (ref "R67")
      (value "4.7R")
      (footprint "R0603")
      (description "High Precision-High Stability Chip Resistor Thin Film 0603 4.7Ohm 0.5% Paper T/R")
      (fields
        (field (name "MANUFACTURER") "Yageo")
        (field (name "MANUFACTURER PART NUMBER") "RT0603DRD074R7L")
        (field (name "TOLERANCE") "0.5%")
        (field (name "CASE/PACKAGE") "0603")
      )
      (libsource (lib "Power2Go - REV05") (part "R_0603_4.7R_0.5%_1/10W"))
    )
    (comp (ref "R68")
      (value "1kR")
      (footprint "R0603")
      (description "Res Thin Film 0603 1K Ohm 0.5% 0.063W(1/16W) ±25ppm/C Pad SMD Automotive T/R")
      (fields
        (field (name "MANUFACTURER") "Susumu")
        (field (name "MANUFACTURER PART NUMBER") "RR0816P-102-D")
        (field (name "CASE/PACKAGE") "0603")
        (field (name "RESISTANCE TOLERANCE") "0.5%")
      )
      (libsource (lib "Power2Go - REV05") (part "R_0603_1kR_0.5%_1/16W_25PPM"))
    )
    (comp (ref "R69")
      (value "240kR")
      (footprint "R0603")
      (description "Res Thin Film 1.6 x 0.8 mm 240K Ohm 0.5% 0.063W(1/16W) 25ppm/ C Molded SMD T/R")
      (fields
        (field (name "MANUFACTURER") "Susumu")
        (field (name "MANUFACTURER PART NUMBER") "RR0816P-244-D")
        (field (name "TOLERANCE") "0.5%")
        (field (name "CASE CODE (IMPERIAL)") "0603")
      )
      (libsource (lib "Power2Go - REV05") (part "R_0603_240kR_0.5%_1/16W_25PPM"))
    )
    (comp (ref "R70")
      (value "240kR")
      (footprint "R0603")
      (description "Res Thin Film 1.6 x 0.8 mm 240K Ohm 0.5% 0.063W(1/16W) 25ppm/ C Molded SMD T/R")
      (fields
        (field (name "MANUFACTURER") "Susumu")
        (field (name "MANUFACTURER PART NUMBER") "RR0816P-244-D")
        (field (name "TOLERANCE") "0.5%")
        (field (name "CASE CODE (IMPERIAL)") "0603")
      )
      (libsource (lib "Power2Go - REV05") (part "R_0603_240kR_0.5%_1/16W_25PPM"))
    )
    (comp (ref "R71")
      (value "240kR")
      (footprint "R0603")
      (description "Res Thin Film 1.6 x 0.8 mm 240K Ohm 0.5% 0.063W(1/16W) 25ppm/ C Molded SMD T/R")
      (fields
        (field (name "MANUFACTURER") "Susumu")
        (field (name "MANUFACTURER PART NUMBER") "RR0816P-244-D")
        (field (name "TOLERANCE") "0.5%")
        (field (name "CASE CODE (IMPERIAL)") "0603")
      )
      (libsource (lib "Power2Go - REV05") (part "R_0603_240kR_0.5%_1/16W_25PPM"))
    )
    (comp (ref "R72")
      (value "240kR")
      (footprint "R0603")
      (description "Res Thin Film 1.6 x 0.8 mm 240K Ohm 0.5% 0.063W(1/16W) 25ppm/ C Molded SMD T/R")
      (fields
        (field (name "MANUFACTURER") "Susumu")
        (field (name "MANUFACTURER PART NUMBER") "RR0816P-244-D")
        (field (name "TOLERANCE") "0.5%")
        (field (name "CASE CODE (IMPERIAL)") "0603")
      )
      (libsource (lib "Power2Go - REV05") (part "R_0603_240kR_0.5%_1/16W_25PPM"))
    )
    (comp (ref "R73")
      (value "240kR")
      (footprint "R0603")
      (description "Res Thin Film 1.6 x 0.8 mm 240K Ohm 0.5% 0.063W(1/16W) 25ppm/ C Molded SMD T/R")
      (fields
        (field (name "MANUFACTURER") "Susumu")
        (field (name "MANUFACTURER PART NUMBER") "RR0816P-244-D")
        (field (name "TOLERANCE") "0.5%")
        (field (name "CASE CODE (IMPERIAL)") "0603")
      )
      (libsource (lib "Power2Go - REV05") (part "R_0603_240kR_0.5%_1/16W_25PPM"))
    )
    (comp (ref "R74")
      (value "240kR")
      (footprint "R0603")
      (description "Res Thin Film 1.6 x 0.8 mm 240K Ohm 0.5% 0.063W(1/16W) 25ppm/ C Molded SMD T/R")
      (fields
        (field (name "MANUFACTURER") "Susumu")
        (field (name "MANUFACTURER PART NUMBER") "RR0816P-244-D")
        (field (name "TOLERANCE") "0.5%")
        (field (name "CASE CODE (IMPERIAL)") "0603")
      )
      (libsource (lib "Power2Go - REV05") (part "R_0603_240kR_0.5%_1/16W_25PPM"))
    )
    (comp (ref "R75")
      (value "240kR")
      (footprint "R0603")
      (description "Res Thin Film 1.6 x 0.8 mm 240K Ohm 0.5% 0.063W(1/16W) 25ppm/ C Molded SMD T/R")
      (fields
        (field (name "MANUFACTURER") "Susumu")
        (field (name "MANUFACTURER PART NUMBER") "RR0816P-244-D")
        (field (name "TOLERANCE") "0.5%")
        (field (name "CASE CODE (IMPERIAL)") "0603")
      )
      (libsource (lib "Power2Go - REV05") (part "R_0603_240kR_0.5%_1/16W_25PPM"))
    )
    (comp (ref "R76")
      (value "1kR")
      (footprint "R0603")
      (description "Res Thin Film 0603 1K Ohm 0.5% 0.063W(1/16W) ±25ppm/C Pad SMD Automotive T/R")
      (fields
        (field (name "MANUFACTURER") "Susumu")
        (field (name "MANUFACTURER PART NUMBER") "RR0816P-102-D")
        (field (name "CASE/PACKAGE") "0603")
        (field (name "RESISTANCE TOLERANCE") "0.5%")
      )
      (libsource (lib "Power2Go - REV05") (part "R_0603_1kR_0.5%_1/16W_25PPM"))
    )
    (comp (ref "R77")
      (value "1kR")
      (footprint "R0603")
      (description "Res Thin Film 0603 1K Ohm 0.5% 0.063W(1/16W) ±25ppm/C Pad SMD Automotive T/R")
      (fields
        (field (name "MANUFACTURER") "Susumu")
        (field (name "MANUFACTURER PART NUMBER") "RR0816P-102-D")
        (field (name "CASE/PACKAGE") "0603")
        (field (name "RESISTANCE TOLERANCE") "0.5%")
      )
      (libsource (lib "Power2Go - REV05") (part "R_0603_1kR_0.5%_1/16W_25PPM"))
    )
    (comp (ref "R78")
      (value "4.7R")
      (footprint "R0603")
      (description "High Precision-High Stability Chip Resistor Thin Film 0603 4.7Ohm 0.5% Paper T/R")
      (fields
        (field (name "MANUFACTURER") "Yageo")
        (field (name "MANUFACTURER PART NUMBER") "RT0603DRD074R7L")
        (field (name "TOLERANCE") "0.5%")
        (field (name "CASE/PACKAGE") "0603")
      )
      (libsource (lib "Power2Go - REV05") (part "R_0603_4.7R_0.5%_1/10W"))
    )
    (comp (ref "R79")
      (value "1kR")
      (footprint "R0603")
      (description "Res Thin Film 0603 1K Ohm 0.5% 0.063W(1/16W) ±25ppm/C Pad SMD Automotive T/R")
      (fields
        (field (name "MANUFACTURER") "Susumu")
        (field (name "MANUFACTURER PART NUMBER") "RR0816P-102-D")
        (field (name "CASE/PACKAGE") "0603")
        (field (name "RESISTANCE TOLERANCE") "0.5%")
      )
      (libsource (lib "Power2Go - REV05") (part "R_0603_1kR_0.5%_1/16W_25PPM"))
    )
    (comp (ref "R80")
      (value "4.7R")
      (footprint "R0603")
      (description "High Precision-High Stability Chip Resistor Thin Film 0603 4.7Ohm 0.5% Paper T/R")
      (fields
        (field (name "MANUFACTURER") "Yageo")
        (field (name "MANUFACTURER PART NUMBER") "RT0603DRD074R7L")
        (field (name "TOLERANCE") "0.5%")
        (field (name "CASE/PACKAGE") "0603")
      )
      (libsource (lib "Power2Go - REV05") (part "R_0603_4.7R_0.5%_1/10W"))
    )
    (comp (ref "R81")
      (value "1kR")
      (footprint "R0603")
      (description "Res Thin Film 0603 1K Ohm 0.5% 0.063W(1/16W) ±25ppm/C Pad SMD Automotive T/R")
      (fields
        (field (name "MANUFACTURER") "Susumu")
        (field (name "MANUFACTURER PART NUMBER") "RR0816P-102-D")
        (field (name "CASE/PACKAGE") "0603")
        (field (name "RESISTANCE TOLERANCE") "0.5%")
      )
      (libsource (lib "Power2Go - REV05") (part "R_0603_1kR_0.5%_1/16W_25PPM"))
    )
    (comp (ref "R93")
      (value "Resistor")
      (footprint "RESC 0805/2012")
      (description "RESISTOR SMD FILME 47 OHM 1% 1/2W 0805")
      (fields
        (field (name "MANUFACTURER PART NUMBER") "ERJ-P06F47R0V")
        (field (name "PARAMETER 2") "0805")
        (field (name "PARAMETER 1") "47R")
        (field (name "MANUFACTURER") "Panasonic")
        (field (name "AUTHOR") "Esdras Bahiano")
      )
      (libsource (lib "LIB_DE_COMPONENTES") (part "Resistor"))
    )
    (comp (ref "R94")
      (value "Resistor")
      (footprint "RESC 0805/2012")
      (description "RESISTOR SMD FILME 47 OHM 1% 1/2W 0805")
      (fields
        (field (name "MANUFACTURER PART NUMBER") "ERJ-P06F47R0V")
        (field (name "PARAMETER 2") "0805")
        (field (name "PARAMETER 1") "47R")
        (field (name "MANUFACTURER") "Panasonic")
        (field (name "AUTHOR") "Esdras Bahiano")
      )
      (libsource (lib "LIB_DE_COMPONENTES") (part "Resistor"))
    )
    (comp (ref "R130")
      (value "Resistor")
      (footprint "RESC 0805/2012")
      (description "RESISTOR SMD FILME 47 OHM 1% 1/2W 0805")
      (fields
        (field (name "MANUFACTURER PART NUMBER") "ERJ-P06F47R0V")
        (field (name "PARAMETER 2") "0805")
        (field (name "PARAMETER 1") "47R")
        (field (name "MANUFACTURER") "Panasonic")
        (field (name "AUTHOR") "Esdras Bahiano")
      )
      (libsource (lib "LIB_DE_COMPONENTES") (part "Resistor"))
    )
    (comp (ref "R131")
      (value "Resistor")
      (footprint "RESC 0805/2012")
      (description "RESISTOR SMD FILME 47 OHM 1% 1/2W 0805")
      (fields
        (field (name "MANUFACTURER PART NUMBER") "ERJ-P06F47R0V")
        (field (name "PARAMETER 2") "0805")
        (field (name "PARAMETER 1") "47R")
        (field (name "MANUFACTURER") "Panasonic")
        (field (name "AUTHOR") "Esdras Bahiano")
      )
      (libsource (lib "LIB_DE_COMPONENTES") (part "Resistor"))
    )
    (comp (ref "TP2")
      (value "S2761-46R")
      (footprint "TP_S276146R")
      (fields (field (name "MANUFACTURER") "Harwin"))
      (libsource (lib "Power2Go - REV05") (part "TP_S2761-46R_SMT"))
    )
    (comp (ref "TP3")
      (value "S2761-46R")
      (footprint "TP_S276146R")
      (fields (field (name "MANUFACTURER") "Harwin"))
      (libsource (lib "Power2Go - REV05") (part "TP_S2761-46R_SMT"))
    )
    (comp (ref "TP4")
      (value "S2761-46R")
      (footprint "TP_S276146R")
      (fields (field (name "MANUFACTURER") "Harwin"))
      (libsource (lib "Power2Go - REV05") (part "TP_S2761-46R_SMT"))
    )
    (comp (ref "TR1")
      (value "IVY-CT-PCB-03-65A")
      (footprint "CT IVY")
      (description "IVY-CT-PCB-03-65A High Accuracy 0.1 Class 65A 2000:1 10ohm Micro PCB Mount CT Current Transformer")
      (libsource (lib "Power2Go - REV05") (part "TR_IVY-CT-PCB-03-65A"))
    )
    (comp (ref "TR2")
      (value "IVY-CT-PCB-03-65A")
      (footprint "CT IVY")
      (description "IVY-CT-PCB-03-65A High Accuracy 0.1 Class 65A 2000:1 10ohm Micro PCB Mount CT Current Transformer")
      (libsource (lib "Power2Go - REV05") (part "TR_IVY-CT-PCB-03-65A"))
    )
    (comp (ref "TR3")
      (value "IVY-CT-PCB-03-65A")
      (footprint "CT IVY")
      (description "IVY-CT-PCB-03-65A High Accuracy 0.1 Class 65A 2000:1 10ohm Micro PCB Mount CT Current Transformer")
      (libsource (lib "Power2Go - REV05") (part "TR_IVY-CT-PCB-03-65A"))
    )
    (comp (ref "U5")
      (value "ATM90E32AS")
      (footprint "TQFP-48")
      (description "Smart Energy SoC, 3 - 3.6 VCC, -40 to 85 degC, TQFP-48, RoHS")
      (fields
        (field (name "MANUFACTURER") "Microchip")
        (field (name "MANUFACTURER PART NUMBER") "ATM90E32AS-AU-Y")
      )
      (libsource (lib "Power2Go - REV05") (part "U_ATM90E32AS_TQFP-48"))
    )
    (comp (ref "VR1")
      (value "B72650M0271K072")
      (footprint "MOV3225")
      (description "Varistor, 350V, 8.6J, Surface Mount")
      (fields (field (name "MANUFACTURER") "TDK EPCOS") (field (name "POWER") "100mW"))
      (libsource (lib "Power2Go - REV05") (part "VR_SMT_430V_B72650M0271K072"))
    )
    (comp (ref "VR2")
      (value "B72650M0271K072")
      (footprint "MOV3225")
      (description "Varistor, 350V, 8.6J, Surface Mount")
      (fields (field (name "MANUFACTURER") "TDK EPCOS") (field (name "POWER") "100mW"))
      (libsource (lib "Power2Go - REV05") (part "VR_SMT_430V_B72650M0271K072"))
    )
    (comp (ref "VR3")
      (value "B72650M0271K072")
      (footprint "MOV3225")
      (description "Varistor, 350V, 8.6J, Surface Mount")
      (fields (field (name "MANUFACTURER") "TDK EPCOS") (field (name "POWER") "100mW"))
      (libsource (lib "Power2Go - REV05") (part "VR_SMT_430V_B72650M0271K072"))
    )
    (comp (ref "VR4")
      (value "B72650M0271K072")
      (footprint "MOV3225")
      (description "Varistor, 350V, 8.6J, Surface Mount")
      (fields (field (name "MANUFACTURER") "TDK EPCOS") (field (name "POWER") "100mW"))
      (libsource (lib "Power2Go - REV05") (part "VR_SMT_430V_B72650M0271K072"))
    )
    (comp (ref "VR5")
      (value "B72650M0271K072")
      (footprint "MOV3225")
      (description "Varistor, 350V, 8.6J, Surface Mount")
      (fields (field (name "MANUFACTURER") "TDK EPCOS") (field (name "POWER") "100mW"))
      (libsource (lib "Power2Go - REV05") (part "VR_SMT_430V_B72650M0271K072"))
    )
    (comp (ref "VR6")
      (value "B72650M0271K072")
      (footprint "MOV3225")
      (description "Varistor, 350V, 8.6J, Surface Mount")
      (fields (field (name "MANUFACTURER") "TDK EPCOS") (field (name "POWER") "100mW"))
      (libsource (lib "Power2Go - REV05") (part "VR_SMT_430V_B72650M0271K072"))
    )
    (comp (ref "VR7")
      (value "B72650M0271K072")
      (footprint "MOV3225")
      (description "Varistor, 350V, 8.6J, Surface Mount")
      (fields (field (name "MANUFACTURER") "TDK EPCOS") (field (name "POWER") "100mW"))
      (libsource (lib "Power2Go - REV05") (part "VR_SMT_430V_B72650M0271K072"))
    )
    (comp (ref "Y3")
      (value "Y_16.384MHZ")
      (footprint "Y50MHz")
      (description "Crystal 16.384MHz 18pF 4-Pin 3225 T/R")
      (fields
        (field (name "MANUFACTURER") "ECS International")
        (field (name "MANUFACTURER PART NUMBER") "ECS-163.84-18-33-JGN-TR3")
      )
      (libsource (lib "Power2Go - REV05") (part "Y_16.384MHZ"))
    )
  )
  (nets
    (net (code "5") (name "+3.3V_ISO") (class "Default")
      (node (ref "C19") (pin "2") (pinfunction "2_2") (pintype "passive"))
      (node (ref "C20") (pin "2") (pinfunction "2_2") (pintype "passive"))
      (node (ref "R34") (pin "2") (pinfunction "2_2") (pintype "passive"))
      (node (ref "R39") (pin "2") (pinfunction "2_2") (pintype "passive"))
      (node (ref "R40") (pin "2") (pinfunction "2_2") (pintype "passive"))
      (node (ref "R41") (pin "2") (pinfunction "2_2") (pintype "passive"))
      (node (ref "R42") (pin "2") (pinfunction "2_2") (pintype "passive"))
      (node (ref "U5") (pin "1") (pinfunction "AVDD_1") (pintype "passive"))
      (node (ref "U5") (pin "48") (pinfunction "DVDD_48") (pintype "passive"))
    )
    (net (code "6") (name "+12V_RELAY") (class "Default")
      (node (ref "C79") (pin "2") (pinfunction "2_2") (pintype "passive"))
      (node (ref "C80") (pin "2") (pinfunction "2_2") (pintype "passive"))
      (node (ref "C81") (pin "2") (pinfunction "2_2") (pintype "passive"))
      (node (ref "C82") (pin "2") (pinfunction "2_2") (pintype "passive"))
      (node (ref "D10") (pin "1") (pinfunction "K_1") (pintype "passive"))
      (node (ref "D11") (pin "1") (pinfunction "K_1") (pintype "passive"))
      (node (ref "D8") (pin "1") (pinfunction "K_1") (pintype "passive"))
      (node (ref "D9") (pin "1") (pinfunction "K_1") (pintype "passive"))
      (node (ref "K1") (pin "3") (pinfunction "A1_3") (pintype "passive"))
      (node (ref "K2") (pin "3") (pinfunction "A1_3") (pintype "passive"))
      (node (ref "K3") (pin "3") (pinfunction "A1_3") (pintype "passive"))
      (node (ref "K4") (pin "3") (pinfunction "A1_3") (pintype "passive"))
    )
    (net (code "8") (name "/ATM90E_SPI1_CS_ISO") (class "Default")
      (node (ref "R39") (pin "1") (pinfunction "1_1") (pintype "passive"))
      (node (ref "U5") (pin "37") (pinfunction "~{CS}_37") (pintype "passive"))
    )
    (net (code "9") (name "/ATM90E_SPI1_MISO_ISO") (class "Default")
      (node (ref "R42") (pin "1") (pinfunction "1_1") (pintype "passive"))
      (node (ref "U5") (pin "39") (pinfunction "SDO_39") (pintype "passive"))
    )
    (net (code "10") (name "/ATM90E_SPI1_MOSI_ISO") (class "Default")
      (node (ref "R41") (pin "1") (pinfunction "1_1") (pintype "passive"))
      (node (ref "U5") (pin "40") (pinfunction "SDI_40") (pintype "passive"))
    )
    (net (code "11") (name "/ATM90E_SPI1_SCLK_ISO") (class "Default")
      (node (ref "R40") (pin "1") (pinfunction "1_1") (pintype "passive"))
      (node (ref "U5") (pin "38") (pinfunction "SCLK_38") (pintype "passive"))
    )
    (net (code "12") (name "/CHARGE_CTL_NEUTRAL") (class "Default")
      (node (ref "R36") (pin "1") (pinfunction "1_1") (pintype "passive"))
    )
    (net (code "13") (name "/CHARGE_CTL_PHASE 1") (class "Default")
      (node (ref "R30") (pin "1") (pinfunction "1_1") (pintype "passive"))
    )
    (net (code "14") (name "/CHARGE_CTL_PHASE 2") (class "Default")
      (node (ref "R31") (pin "1") (pinfunction "1_1") (pintype "passive"))
    )
    (net (code "15") (name "/CHARGE_CTL_PHASE 3") (class "Default")
      (node (ref "R35") (pin "1") (pinfunction "1_1") (pintype "passive"))
    )
    (net (code "16") (name "/IAN") (class "Default")
      (node (ref "C31") (pin "2") (pinfunction "2_2") (pintype "passive"))
      (node (ref "R55") (pin "1") (pinfunction "1_1") (pintype "passive"))
      (node (ref "U5") (pin "4") (pinfunction "I1N_4") (pintype "passive"))
    )
    (net (code "17") (name "/IAP") (class "Default")
      (node (ref "C28") (pin "1") (pinfunction "1_1") (pintype "passive"))
      (node (ref "R50") (pin "1") (pinfunction "1_1") (pintype "passive"))
      (node (ref "U5") (pin "3") (pinfunction "I1P_3") (pintype "passive"))
    )
    (net (code "18") (name "/IBN") (class "Default")
      (node (ref "C35") (pin "2") (pinfunction "2_2") (pintype "passive"))
      (node (ref "R68") (pin "1") (pinfunction "1_1") (pintype "passive"))
      (node (ref "U5") (pin "6") (pinfunction "I2N_6") (pintype "passive"))
    )
    (net (code "19") (name "/IBP") (class "Default")
      (node (ref "C32") (pin "1") (pinfunction "1_1") (pintype "passive"))
      (node (ref "R63") (pin "1") (pinfunction "1_1") (pintype "passive"))
      (node (ref "U5") (pin "5") (pinfunction "I2P_5") (pintype "passive"))
    )
    (net (code "20") (name "/ICN") (class "Default")
      (node (ref "C39") (pin "2") (pinfunction "2_2") (pintype "passive"))
      (node (ref "R81") (pin "1") (pinfunction "1_1") (pintype "passive"))
      (node (ref "U5") (pin "8") (pinfunction "I3N_8") (pintype "passive"))
    )
    (net (code "21") (name "/ICP") (class "Default")
      (node (ref "C36") (pin "1") (pinfunction "1_1") (pintype "passive"))
      (node (ref "R76") (pin "1") (pinfunction "1_1") (pintype "passive"))
      (node (ref "U5") (pin "7") (pinfunction "I3P_7") (pintype "passive"))
    )
    (net (code "22") (name "/IRQ0_ATM90E_ISO") (class "Default")
      (node (ref "U5") (pin "30") (pinfunction "IRQ0_30") (pintype "passive"))
    )
    (net (code "23") (name "/IRQ1_ATM90E_ISO") (class "Default")
      (node (ref "U5") (pin "31") (pinfunction "IRQ1_31") (pintype "passive"))
    )
    (net (code "24") (name "/PM0_ATM90E_ISO") (class "Default")
      (node (ref "U5") (pin "33") (pinfunction "PM0_33") (pintype "passive"))
    )
    (net (code "25") (name "/PM1_ATM90E_ISO") (class "Default")
      (node (ref "U5") (pin "34") (pinfunction "PM1_34") (pintype "passive"))
    )
    (net (code "26") (name "/VAN") (class "Default")
      (node (ref "C30") (pin "1") (pinfunction "1_1") (pintype "passive"))
      (node (ref "R53") (pin "1") (pinfunction "1_1") (pintype "passive"))
      (node (ref "U5") (pin "14") (pinfunction "V1N_14") (pintype "passive"))
    )
    (net (code "27") (name "/VAP") (class "Default")
      (node (ref "C29") (pin "1") (pinfunction "1_1") (pintype "passive"))
      (node (ref "R49") (pin "1") (pinfunction "1_1") (pintype "passive"))
      (node (ref "R52") (pin "1") (pinfunction "1_1") (pintype "passive"))
      (node (ref "TP2") (pin "1") (pinfunction "1_1") (pintype "passive"))
      (node (ref "U5") (pin "13") (pinfunction "V1P_13") (pintype "passive"))
    )
    (net (code "28") (name "/VBN") (class "Default")
      (node (ref "C34") (pin "1") (pinfunction "1_1") (pintype "passive"))
      (node (ref "R66") (pin "1") (pinfunction "1_1") (pintype "passive"))
      (node (ref "U5") (pin "16") (pinfunction "V2N_16") (pintype "passive"))
    )
    (net (code "29") (name "/VBP") (class "Default")
      (node (ref "C33") (pin "1") (pinfunction "1_1") (pintype "passive"))
      (node (ref "R62") (pin "1") (pinfunction "1_1") (pintype "passive"))
      (node (ref "R64") (pin "1") (pinfunction "1_1") (pintype "passive"))
      (node (ref "TP3") (pin "1") (pinfunction "1_1") (pintype "passive"))
      (node (ref "U5") (pin "15") (pinfunction "V2P_15") (pintype "passive"))
    )
    (net (code "30") (name "/VCN") (class "Default")
      (node (ref "C38") (pin "1") (pinfunction "1_1") (pintype "passive"))
      (node (ref "R79") (pin "1") (pinfunction "1_1") (pintype "passive"))
      (node (ref "U5") (pin "18") (pinfunction "V3N_18") (pintype "passive"))
    )
    (net (code "31") (name "/VCP") (class "Default")
      (node (ref "C37") (pin "1") (pinfunction "1_1") (pintype "passive"))
      (node (ref "R75") (pin "1") (pinfunction "1_1") (pintype "passive"))
      (node (ref "R77") (pin "1") (pinfunction "1_1") (pintype "passive"))
      (node (ref "TP4") (pin "1") (pinfunction "1_1") (pintype "passive"))
      (node (ref "U5") (pin "17") (pinfunction "V3P_17") (pintype "passive"))
    )
    (net (code "32") (name "/WO_ATM90E_ISO") (class "Default")
      (node (ref "U5") (pin "29") (pinfunction "WARNOUT_29") (pintype "passive"))
    )
    (net (code "33") (name "/~{RST}_ATM90E_ISO") (class "Default")
      (node (ref "C22") (pin "1") (pinfunction "1_1") (pintype "passive"))
      (node (ref "R34") (pin "1") (pinfunction "1_1") (pintype "passive"))
      (node (ref "U5") (pin "41") (pinfunction "~{RESET}_41") (pintype "passive"))
    )
    (net (code "34") (name "EARTH") (class "Default")
      (node (ref "MECH1") (pin "1") (pinfunction "1_1") (pintype "passive"))
      (node (ref "MECH2") (pin "1") (pinfunction "1_1") (pintype "passive"))
      (node (ref "P10") (pin "1") (pinfunction "1_1") (pintype "passive"))
      (node (ref "P10") (pin "2") (pinfunction "2_2") (pintype "passive"))
      (node (ref "P10") (pin "3") (pinfunction "3_3") (pintype "passive"))
      (node (ref "P10") (pin "4") (pinfunction "4_4") (pintype "passive"))
      (node (ref "P15") (pin "1") (pinfunction "1_1") (pintype "passive"))
      (node (ref "P15") (pin "2") (pinfunction "2_2") (pintype "passive"))
      (node (ref "P15") (pin "3") (pinfunction "3_3") (pintype "passive"))
      (node (ref "P15") (pin "4") (pinfunction "4_4") (pintype "passive"))
      (node (ref "Q3") (pin "2") (pinfunction "S_2") (pintype "passive"))
      (node (ref "Q4") (pin "2") (pinfunction "S_2") (pintype "passive"))
      (node (ref "Q5") (pin "2") (pinfunction "S_2") (pintype "passive"))
      (node (ref "Q6") (pin "2") (pinfunction "S_2") (pintype "passive"))
      (node (ref "R32") (pin "1") (pinfunction "1_1") (pintype "passive"))
      (node (ref "R33") (pin "1") (pinfunction "1_1") (pintype "passive"))
      (node (ref "R37") (pin "1") (pinfunction "1_1") (pintype "passive"))
      (node (ref "R38") (pin "1") (pinfunction "1_1") (pintype "passive"))
      (node (ref "VR4") (pin "2") (pinfunction "2_2") (pintype "passive"))
      (node (ref "VR5") (pin "2") (pinfunction "2_2") (pintype "passive"))
      (node (ref "VR6") (pin "2") (pinfunction "2_2") (pintype "passive"))
      (node (ref "VR7") (pin "2") (pinfunction "2_2") (pintype "passive"))
    )
    (net (code "35") (name "GND_3.3V_ISO") (class "Default")
      (node (ref "C19") (pin "1") (pinfunction "1_1") (pintype "passive"))
      (node (ref "C20") (pin "1") (pinfunction "1_1") (pintype "passive"))
      (node (ref "C21") (pin "1") (pinfunction "1_1") (pintype "passive"))
      (node (ref "C22") (pin "2") (pinfunction "2_2") (pintype "passive"))
      (node (ref "C23") (pin "2") (pinfunction "2_2") (pintype "passive"))
      (node (ref "C24") (pin "1") (pinfunction "1_1") (pintype "passive"))
      (node (ref "C25") (pin "2") (pinfunction "2_2") (pintype "passive"))
      (node (ref "C26") (pin "1") (pinfunction "1_1") (pintype "passive"))
      (node (ref "C27") (pin "1") (pinfunction "1_1") (pintype "passive"))
      (node (ref "C28") (pin "2") (pinfunction "2_2") (pintype "passive"))
      (node (ref "C29") (pin "2") (pinfunction "2_2") (pintype "passive"))
      (node (ref "C30") (pin "2") (pinfunction "2_2") (pintype "passive"))
      (node (ref "C31") (pin "1") (pinfunction "1_1") (pintype "passive"))
      (node (ref "C32") (pin "2") (pinfunction "2_2") (pintype "passive"))
      (node (ref "C33") (pin "2") (pinfunction "2_2") (pintype "passive"))
      (node (ref "C34") (pin "2") (pinfunction "2_2") (pintype "passive"))
      (node (ref "C35") (pin "1") (pinfunction "1_1") (pintype "passive"))
      (node (ref "C36") (pin "2") (pinfunction "2_2") (pintype "passive"))
      (node (ref "C37") (pin "2") (pinfunction "2_2") (pintype "passive"))
      (node (ref "C38") (pin "2") (pinfunction "2_2") (pintype "passive"))
      (node (ref "C39") (pin "1") (pinfunction "1_1") (pintype "passive"))
      (node (ref "K4") (pin "1") (pinfunction "NO_1") (pintype "passive"))
      (node (ref "P9") (pin "1") (pinfunction "1_1") (pintype "passive"))
      (node (ref "P9") (pin "2") (pinfunction "2_2") (pintype "passive"))
      (node (ref "P9") (pin "3") (pinfunction "3_3") (pintype "passive"))
      (node (ref "P9") (pin "4") (pinfunction "4_4") (pintype "passive"))
      (node (ref "R51") (pin "2") (pinfunction "2_2") (pintype "passive"))
      (node (ref "R52") (pin "2") (pinfunction "2_2") (pintype "passive"))
      (node (ref "R53") (pin "2") (pinfunction "2_2") (pintype "passive"))
      (node (ref "R54") (pin "1") (pinfunction "1_1") (pintype "passive"))
      (node (ref "R64") (pin "2") (pinfunction "2_2") (pintype "passive"))
      (node (ref "R65") (pin "2") (pinfunction "2_2") (pintype "passive"))
      (node (ref "R66") (pin "2") (pinfunction "2_2") (pintype "passive"))
      (node (ref "R67") (pin "1") (pinfunction "1_1") (pintype "passive"))
      (node (ref "R77") (pin "2") (pinfunction "2_2") (pintype "passive"))
      (node (ref "R78") (pin "2") (pinfunction "2_2") (pintype "passive"))
      (node (ref "R79") (pin "2") (pinfunction "2_2") (pintype "passive"))
      (node (ref "R80") (pin "1") (pinfunction "1_1") (pintype "passive"))
      (node (ref "U5") (pin "10") (pinfunction "IC_2_10") (pintype "passive"))
      (node (ref "U5") (pin "12") (pinfunction "AGND_2_12") (pintype "passive"))
      (node (ref "U5") (pin "19") (pinfunction "DGND_1_19") (pintype "passive"))
      (node (ref "U5") (pin "2") (pinfunction "AGND_1_2") (pintype "passive"))
      (node (ref "U5") (pin "32") (pinfunction "TEST_32") (pintype "passive"))
      (node (ref "U5") (pin "36") (pinfunction "IC_3_36") (pintype "passive"))
      (node (ref "U5") (pin "44") (pinfunction "DGND_2_44") (pintype "passive"))
      (node (ref "U5") (pin "47") (pinfunction "DGND_3_47") (pintype "passive"))
      (node (ref "U5") (pin "9") (pinfunction "IC_1_9") (pintype "passive"))
      (node (ref "VR1") (pin "2") (pinfunction "2_2") (pintype "passive"))
      (node (ref "VR2") (pin "2") (pinfunction "2_2") (pintype "passive"))
      (node (ref "VR3") (pin "2") (pinfunction "2_2") (pintype "passive"))
      (node (ref "VR7") (pin "1") (pinfunction "1_1") (pintype "passive"))
      (node (ref "Y3") (pin "2") (pinfunction "2_2") (pintype "passive"))
      (node (ref "Y3") (pin "4") (pinfunction "4_4") (pintype "passive"))
    )
    (net (code "36") (name "NEUTRAL_OUT") (class "Default")
      (node (ref "K4") (pin "2") (pinfunction "C_2") (pintype "passive"))
      (node (ref "P14") (pin "1") (pinfunction "1_1") (pintype "passive"))
      (node (ref "P14") (pin "2") (pinfunction "2_2") (pintype "passive"))
      (node (ref "P14") (pin "3") (pinfunction "3_3") (pintype "passive"))
      (node (ref "P14") (pin "4") (pinfunction "4_4") (pintype "passive"))
    )
    (net (code "37") (name "Net-(C79-Pad1)") (class "Default")
      (node (ref "C79") (pin "1") (pinfunction "1_1") (pintype "passive"))
      (node (ref "R93") (pin "2") (pinfunction "2_2") (pintype "passive"))
    )
    (net (code "38") (name "Net-(C80-Pad1)") (class "Default")
      (node (ref "C80") (pin "1") (pinfunction "1_1") (pintype "passive"))
      (node (ref "R94") (pin "2") (pinfunction "2_2") (pintype "passive"))
    )
    (net (code "39") (name "Net-(C81-Pad1)") (class "Default")
      (node (ref "C81") (pin "1") (pinfunction "1_1") (pintype "passive"))
      (node (ref "R130") (pin "2") (pinfunction "2_2") (pintype "passive"))
    )
    (net (code "40") (name "Net-(C82-Pad1)") (class "Default")
      (node (ref "C82") (pin "1") (pinfunction "1_1") (pintype "passive"))
      (node (ref "R131") (pin "2") (pinfunction "2_2") (pintype "passive"))
    )
    (net (code "41") (name "Net-(D8-A)") (class "Default")
      (node (ref "D8") (pin "2") (pinfunction "A_2") (pintype "passive"))
      (node (ref "K1") (pin "4") (pinfunction "A2_4") (pintype "passive"))
      (node (ref "Q3") (pin "3") (pinfunction "D_3") (pintype "passive"))
      (node (ref "R93") (pin "1") (pinfunction "1_1") (pintype "passive"))
    )
    (net (code "42") (name "Net-(D9-A)") (class "Default")
      (node (ref "D9") (pin "2") (pinfunction "A_2") (pintype "passive"))
      (node (ref "K2") (pin "4") (pinfunction "A2_4") (pintype "passive"))
      (node (ref "Q4") (pin "3") (pinfunction "D_3") (pintype "passive"))
      (node (ref "R94") (pin "1") (pinfunction "1_1") (pintype "passive"))
    )
    (net (code "43") (name "Net-(D10-A)") (class "Default")
      (node (ref "D10") (pin "2") (pinfunction "A_2") (pintype "passive"))
      (node (ref "K3") (pin "4") (pinfunction "A2_4") (pintype "passive"))
      (node (ref "Q5") (pin "3") (pinfunction "D_3") (pintype "passive"))
      (node (ref "R130") (pin "1") (pinfunction "1_1") (pintype "passive"))
    )
    (net (code "44") (name "Net-(D11-A)") (class "Default")
      (node (ref "D11") (pin "2") (pinfunction "A_2") (pintype "passive"))
      (node (ref "K4") (pin "4") (pinfunction "A2_4") (pintype "passive"))
      (node (ref "Q6") (pin "3") (pinfunction "D_3") (pintype "passive"))
      (node (ref "R131") (pin "1") (pinfunction "1_1") (pintype "passive"))
    )
    (net (code "45") (name "Net-(Q3-G)") (class "Default")
      (node (ref "Q3") (pin "1") (pinfunction "G_1") (pintype "passive"))
      (node (ref "R30") (pin "2") (pinfunction "2_2") (pintype "passive"))
      (node (ref "R32") (pin "2") (pinfunction "2_2") (pintype "passive"))
    )
    (net (code "46") (name "Net-(Q4-G)") (class "Default")
      (node (ref "Q4") (pin "1") (pinfunction "G_1") (pintype "passive"))
      (node (ref "R31") (pin "2") (pinfunction "2_2") (pintype "passive"))
      (node (ref "R33") (pin "2") (pinfunction "2_2") (pintype "passive"))
    )
    (net (code "47") (name "Net-(Q5-G)") (class "Default")
      (node (ref "Q5") (pin "1") (pinfunction "G_1") (pintype "passive"))
      (node (ref "R35") (pin "2") (pinfunction "2_2") (pintype "passive"))
      (node (ref "R37") (pin "2") (pinfunction "2_2") (pintype "passive"))
    )
    (net (code "48") (name "Net-(Q6-G)") (class "Default")
      (node (ref "Q6") (pin "1") (pinfunction "G_1") (pintype "passive"))
      (node (ref "R36") (pin "2") (pinfunction "2_2") (pintype "passive"))
      (node (ref "R38") (pin "2") (pinfunction "2_2") (pintype "passive"))
    )
    (net (code "49") (name "Net-(R43-Pad1)") (class "Default")
      (node (ref "R43") (pin "1") (pinfunction "1_1") (pintype "passive"))
      (node (ref "R44") (pin "2") (pinfunction "2_2") (pintype "passive"))
    )
    (net (code "50") (name "Net-(R44-Pad1)") (class "Default")
      (node (ref "R44") (pin "1") (pinfunction "1_1") (pintype "passive"))
      (node (ref "R48") (pin "2") (pinfunction "2_2") (pintype "passive"))
    )
    (net (code "51") (name "Net-(R45-Pad1)") (class "Default")
      (node (ref "R45") (pin "1") (pinfunction "1_1") (pintype "passive"))
      (node (ref "R46") (pin "2") (pinfunction "2_2") (pintype "passive"))
    )
    (net (code "52") (name "Net-(R45-Pad2)") (class "Default")
      (node (ref "R45") (pin "2") (pinfunction "2_2") (pintype "passive"))
      (node (ref "R48") (pin "1") (pinfunction "1_1") (pintype "passive"))
    )
    (net (code "53") (name "Net-(R46-Pad1)") (class "Default")
      (node (ref "R46") (pin "1") (pinfunction "1_1") (pintype "passive"))
      (node (ref "R47") (pin "2") (pinfunction "2_2") (pintype "passive"))
    )
    (net (code "54") (name "Net-(R47-Pad1)") (class "Default")
      (node (ref "R47") (pin "1") (pinfunction "1_1") (pintype "passive"))
      (node (ref "R49") (pin "2") (pinfunction "2_2") (pintype "passive"))
    )
    (net (code "55") (name "Net-(R56-Pad1)") (class "Default")
      (node (ref "R56") (pin "1") (pinfunction "1_1") (pintype "passive"))
      (node (ref "R57") (pin "2") (pinfunction "2_2") (pintype "passive"))
    )
    (net (code "56") (name "Net-(R57-Pad1)") (class "Default")
      (node (ref "R57") (pin "1") (pinfunction "1_1") (pintype "passive"))
      (node (ref "R58") (pin "2") (pinfunction "2_2") (pintype "passive"))
    )
    (net (code "57") (name "Net-(R58-Pad1)") (class "Default")
      (node (ref "R58") (pin "1") (pinfunction "1_1") (pintype "passive"))
      (node (ref "R59") (pin "2") (pinfunction "2_2") (pintype "passive"))
    )
    (net (code "58") (name "Net-(R59-Pad1)") (class "Default")
      (node (ref "R59") (pin "1") (pinfunction "1_1") (pintype "passive"))
      (node (ref "R60") (pin "2") (pinfunction "2_2") (pintype "passive"))
    )
    (net (code "59") (name "Net-(R60-Pad1)") (class "Default")
      (node (ref "R60") (pin "1") (pinfunction "1_1") (pintype "passive"))
      (node (ref "R61") (pin "2") (pinfunction "2_2") (pintype "passive"))
    )
    (net (code "60") (name "Net-(R61-Pad1)") (class "Default")
      (node (ref "R61") (pin "1") (pinfunction "1_1") (pintype "passive"))
      (node (ref "R62") (pin "2") (pinfunction "2_2") (pintype "passive"))
    )
    (net (code "61") (name "Net-(R69-Pad1)") (class "Default")
      (node (ref "R69") (pin "1") (pinfunction "1_1") (pintype "passive"))
      (node (ref "R70") (pin "2") (pinfunction "2_2") (pintype "passive"))
    )
    (net (code "62") (name "Net-(R70-Pad1)") (class "Default")
      (node (ref "R70") (pin "1") (pinfunction "1_1") (pintype "passive"))
      (node (ref "R71") (pin "2") (pinfunction "2_2") (pintype "passive"))
    )
    (net (code "63") (name "Net-(R71-Pad1)") (class "Default")
      (node (ref "R71") (pin "1") (pinfunction "1_1") (pintype "passive"))
      (node (ref "R72") (pin "2") (pinfunction "2_2") (pintype "passive"))
    )
    (net (code "64") (name "Net-(R72-Pad1)") (class "Default")
      (node (ref "R72") (pin "1") (pinfunction "1_1") (pintype "passive"))
      (node (ref "R73") (pin "2") (pinfunction "2_2") (pintype "passive"))
    )
    (net (code "65") (name "Net-(R73-Pad1)") (class "Default")
      (node (ref "R73") (pin "1") (pinfunction "1_1") (pintype "passive"))
      (node (ref "R74") (pin "2") (pinfunction "2_2") (pintype "passive"))
    )
    (net (code "66") (name "Net-(R74-Pad1)") (class "Default")
      (node (ref "R74") (pin "1") (pinfunction "1_1") (pintype "passive"))
      (node (ref "R75") (pin "2") (pinfunction "2_2") (pintype "passive"))
    )
    (net (code "67") (name "Net-(TR1-I)") (class "Default")
      (node (ref "R54") (pin "2") (pinfunction "2_2") (pintype "passive"))
      (node (ref "R55") (pin "2") (pinfunction "2_2") (pintype "passive"))
      (node (ref "TR1") (pin "1") (pinfunction "I_1") (pintype "passive"))
    )
    (net (code "68") (name "Net-(TR1-K)") (class "Default")
      (node (ref "R50") (pin "2") (pinfunction "2_2") (pintype "passive"))
      (node (ref "R51") (pin "1") (pinfunction "1_1") (pintype "passive"))
      (node (ref "TR1") (pin "4") (pinfunction "K_4") (pintype "passive"))
    )
    (net (code "69") (name "Net-(TR2-I)") (class "Default")
      (node (ref "R67") (pin "2") (pinfunction "2_2") (pintype "passive"))
      (node (ref "R68") (pin "2") (pinfunction "2_2") (pintype "passive"))
      (node (ref "TR2") (pin "1") (pinfunction "I_1") (pintype "passive"))
    )
    (net (code "70") (name "Net-(TR2-K)") (class "Default")
      (node (ref "R63") (pin "2") (pinfunction "2_2") (pintype "passive"))
      (node (ref "R65") (pin "1") (pinfunction "1_1") (pintype "passive"))
      (node (ref "TR2") (pin "4") (pinfunction "K_4") (pintype "passive"))
    )
    (net (code "71") (name "Net-(TR3-I)") (class "Default")
      (node (ref "R80") (pin "2") (pinfunction "2_2") (pintype "passive"))
      (node (ref "R81") (pin "2") (pinfunction "2_2") (pintype "passive"))
      (node (ref "TR3") (pin "1") (pinfunction "I_1") (pintype "passive"))
    )
    (net (code "72") (name "Net-(TR3-K)") (class "Default")
      (node (ref "R76") (pin "2") (pinfunction "2_2") (pintype "passive"))
      (node (ref "R78") (pin "1") (pinfunction "1_1") (pintype "passive"))
      (node (ref "TR3") (pin "4") (pinfunction "K_4") (pintype "passive"))
    )
    (net (code "73") (name "Net-(U5A-VDD18_1)") (class "Default")
      (node (ref "C21") (pin "2") (pinfunction "2_2") (pintype "passive"))
      (node (ref "C23") (pin "1") (pinfunction "1_1") (pintype "passive"))
      (node (ref "U5") (pin "42") (pinfunction "VDD18_1_42") (pintype "passive"))
      (node (ref "U5") (pin "43") (pinfunction "VDD18_2_43") (pintype "passive"))
    )
    (net (code "74") (name "Net-(U5A-VREF)") (class "Default")
      (node (ref "C24") (pin "2") (pinfunction "2_2") (pintype "passive"))
      (node (ref "C25") (pin "1") (pinfunction "1_1") (pintype "passive"))
      (node (ref "U5") (pin "11") (pinfunction "VREF_11") (pintype "passive"))
    )
    (net (code "75") (name "Net-(U5B-OSCI)") (class "Default")
      (node (ref "C26") (pin "2") (pinfunction "2_2") (pintype "passive"))
      (node (ref "U5") (pin "20") (pinfunction "OSCI_20") (pintype "passive"))
      (node (ref "Y3") (pin "1") (pinfunction "1_1") (pintype "passive"))
    )
    (net (code "76") (name "Net-(U5B-OSCO)") (class "Default")
      (node (ref "C27") (pin "2") (pinfunction "2_2") (pintype "passive"))
      (node (ref "U5") (pin "21") (pinfunction "OSCO_21") (pintype "passive"))
      (node (ref "Y3") (pin "3") (pinfunction "3_3") (pintype "passive"))
    )
    (net (code "77") (name "PHASE 1_IN") (class "Default")
      (node (ref "K1") (pin "1") (pinfunction "NO_1") (pintype "passive"))
      (node (ref "P6") (pin "1") (pinfunction "1_1") (pintype "passive"))
      (node (ref "P6") (pin "2") (pinfunction "2_2") (pintype "passive"))
      (node (ref "P6") (pin "3") (pinfunction "3_3") (pintype "passive"))
      (node (ref "P6") (pin "4") (pinfunction "4_4") (pintype "passive"))
      (node (ref "R43") (pin "2") (pinfunction "2_2") (pintype "passive"))
      (node (ref "VR1") (pin "1") (pinfunction "1_1") (pintype "passive"))
      (node (ref "VR4") (pin "1") (pinfunction "1_1") (pintype "passive"))
    )
    (net (code "78") (name "PHASE 1_OUT") (class "Default")
      (node (ref "K1") (pin "2") (pinfunction "C_2") (pintype "passive"))
      (node (ref "P11") (pin "1") (pinfunction "1_1") (pintype "passive"))
      (node (ref "P11") (pin "2") (pinfunction "2_2") (pintype "passive"))
      (node (ref "P11") (pin "3") (pinfunction "3_3") (pintype "passive"))
      (node (ref "P11") (pin "4") (pinfunction "4_4") (pintype "passive"))
    )
    (net (code "79") (name "PHASE 2_IN") (class "Default")
      (node (ref "K2") (pin "1") (pinfunction "NO_1") (pintype "passive"))
      (node (ref "P8") (pin "1") (pinfunction "1_1") (pintype "passive"))
      (node (ref "P8") (pin "2") (pinfunction "2_2") (pintype "passive"))
      (node (ref "P8") (pin "3") (pinfunction "3_3") (pintype "passive"))
      (node (ref "P8") (pin "4") (pinfunction "4_4") (pintype "passive"))
      (node (ref "R56") (pin "2") (pinfunction "2_2") (pintype "passive"))
      (node (ref "VR2") (pin "1") (pinfunction "1_1") (pintype "passive"))
      (node (ref "VR5") (pin "1") (pinfunction "1_1") (pintype "passive"))
    )
    (net (code "80") (name "PHASE 2_OUT") (class "Default")
      (node (ref "K2") (pin "2") (pinfunction "C_2") (pintype "passive"))
      (node (ref "P12") (pin "1") (pinfunction "1_1") (pintype "passive"))
      (node (ref "P12") (pin "2") (pinfunction "2_2") (pintype "passive"))
      (node (ref "P12") (pin "3") (pinfunction "3_3") (pintype "passive"))
      (node (ref "P12") (pin "4") (pinfunction "4_4") (pintype "passive"))
    )
    (net (code "81") (name "PHASE 3_IN") (class "Default")
      (node (ref "K3") (pin "1") (pinfunction "NO_1") (pintype "passive"))
      (node (ref "P7") (pin "1") (pinfunction "1_1") (pintype "passive"))
      (node (ref "P7") (pin "2") (pinfunction "2_2") (pintype "passive"))
      (node (ref "P7") (pin "3") (pinfunction "3_3") (pintype "passive"))
      (node (ref "P7") (pin "4") (pinfunction "4_4") (pintype "passive"))
      (node (ref "R69") (pin "2") (pinfunction "2_2") (pintype "passive"))
      (node (ref "VR3") (pin "1") (pinfunction "1_1") (pintype "passive"))
      (node (ref "VR6") (pin "1") (pinfunction "1_1") (pintype "passive"))
    )
    (net (code "82") (name "PHASE 3_OUT") (class "Default")
      (node (ref "K3") (pin "2") (pinfunction "C_2") (pintype "passive"))
      (node (ref "P13") (pin "1") (pinfunction "1_1") (pintype "passive"))
      (node (ref "P13") (pin "2") (pinfunction "2_2") (pintype "passive"))
      (node (ref "P13") (pin "3") (pinfunction "3_3") (pintype "passive"))
      (node (ref "P13") (pin "4") (pinfunction "4_4") (pintype "passive"))
    )
    (net (code "83") (name "unconnected-(U5B-CF1-Pad25)") (class "Default")
      (node (ref "U5") (pin "25") (pinfunction "CF1_25") (pintype "passive"))
    )
    (net (code "84") (name "unconnected-(U5B-CF2-Pad26)") (class "Default")
      (node (ref "U5") (pin "26") (pinfunction "CF2_26") (pintype "passive"))
    )
    (net (code "85") (name "unconnected-(U5B-CF3-Pad27)") (class "Default")
      (node (ref "U5") (pin "27") (pinfunction "CF3_27") (pintype "passive"))
    )
    (net (code "86") (name "unconnected-(U5B-CF4-Pad28)") (class "Default")
      (node (ref "U5") (pin "28") (pinfunction "CF4_28") (pintype "passive"))
    )
    (net (code "87") (name "unconnected-(U5B-NC_1-Pad35)") (class "Default")
      (node (ref "U5") (pin "35") (pinfunction "NC_1_35") (pintype "passive+no_connect"))
    )
    (net (code "88") (name "unconnected-(U5B-NC_2-Pad45)") (class "Default")
      (node (ref "U5") (pin "45") (pinfunction "NC_2_45") (pintype "passive+no_connect"))
    )
    (net (code "89") (name "unconnected-(U5B-NC_3-Pad46)") (class "Default")
      (node (ref "U5") (pin "46") (pinfunction "NC_3_46") (pintype "passive+no_connect"))
    )
    (net (code "90") (name "unconnected-(U5B-ZX0-Pad22)") (class "Default")
      (node (ref "U5") (pin "22") (pinfunction "ZX0_22") (pintype "passive"))
    )
    (net (code "91") (name "unconnected-(U5B-ZX1-Pad23)") (class "Default")
      (node (ref "U5") (pin "23") (pinfunction "ZX1_23") (pintype "passive"))
    )
    (net (code "92") (name "unconnected-(U5B-ZX2-Pad24)") (class "Default")
      (node (ref "U5") (pin "24") (pinfunction "ZX2_24") (pintype "passive"))
    )
  )
)
